# MDB1986.net
KiCad netlist of a schematic drawn in EAGLE
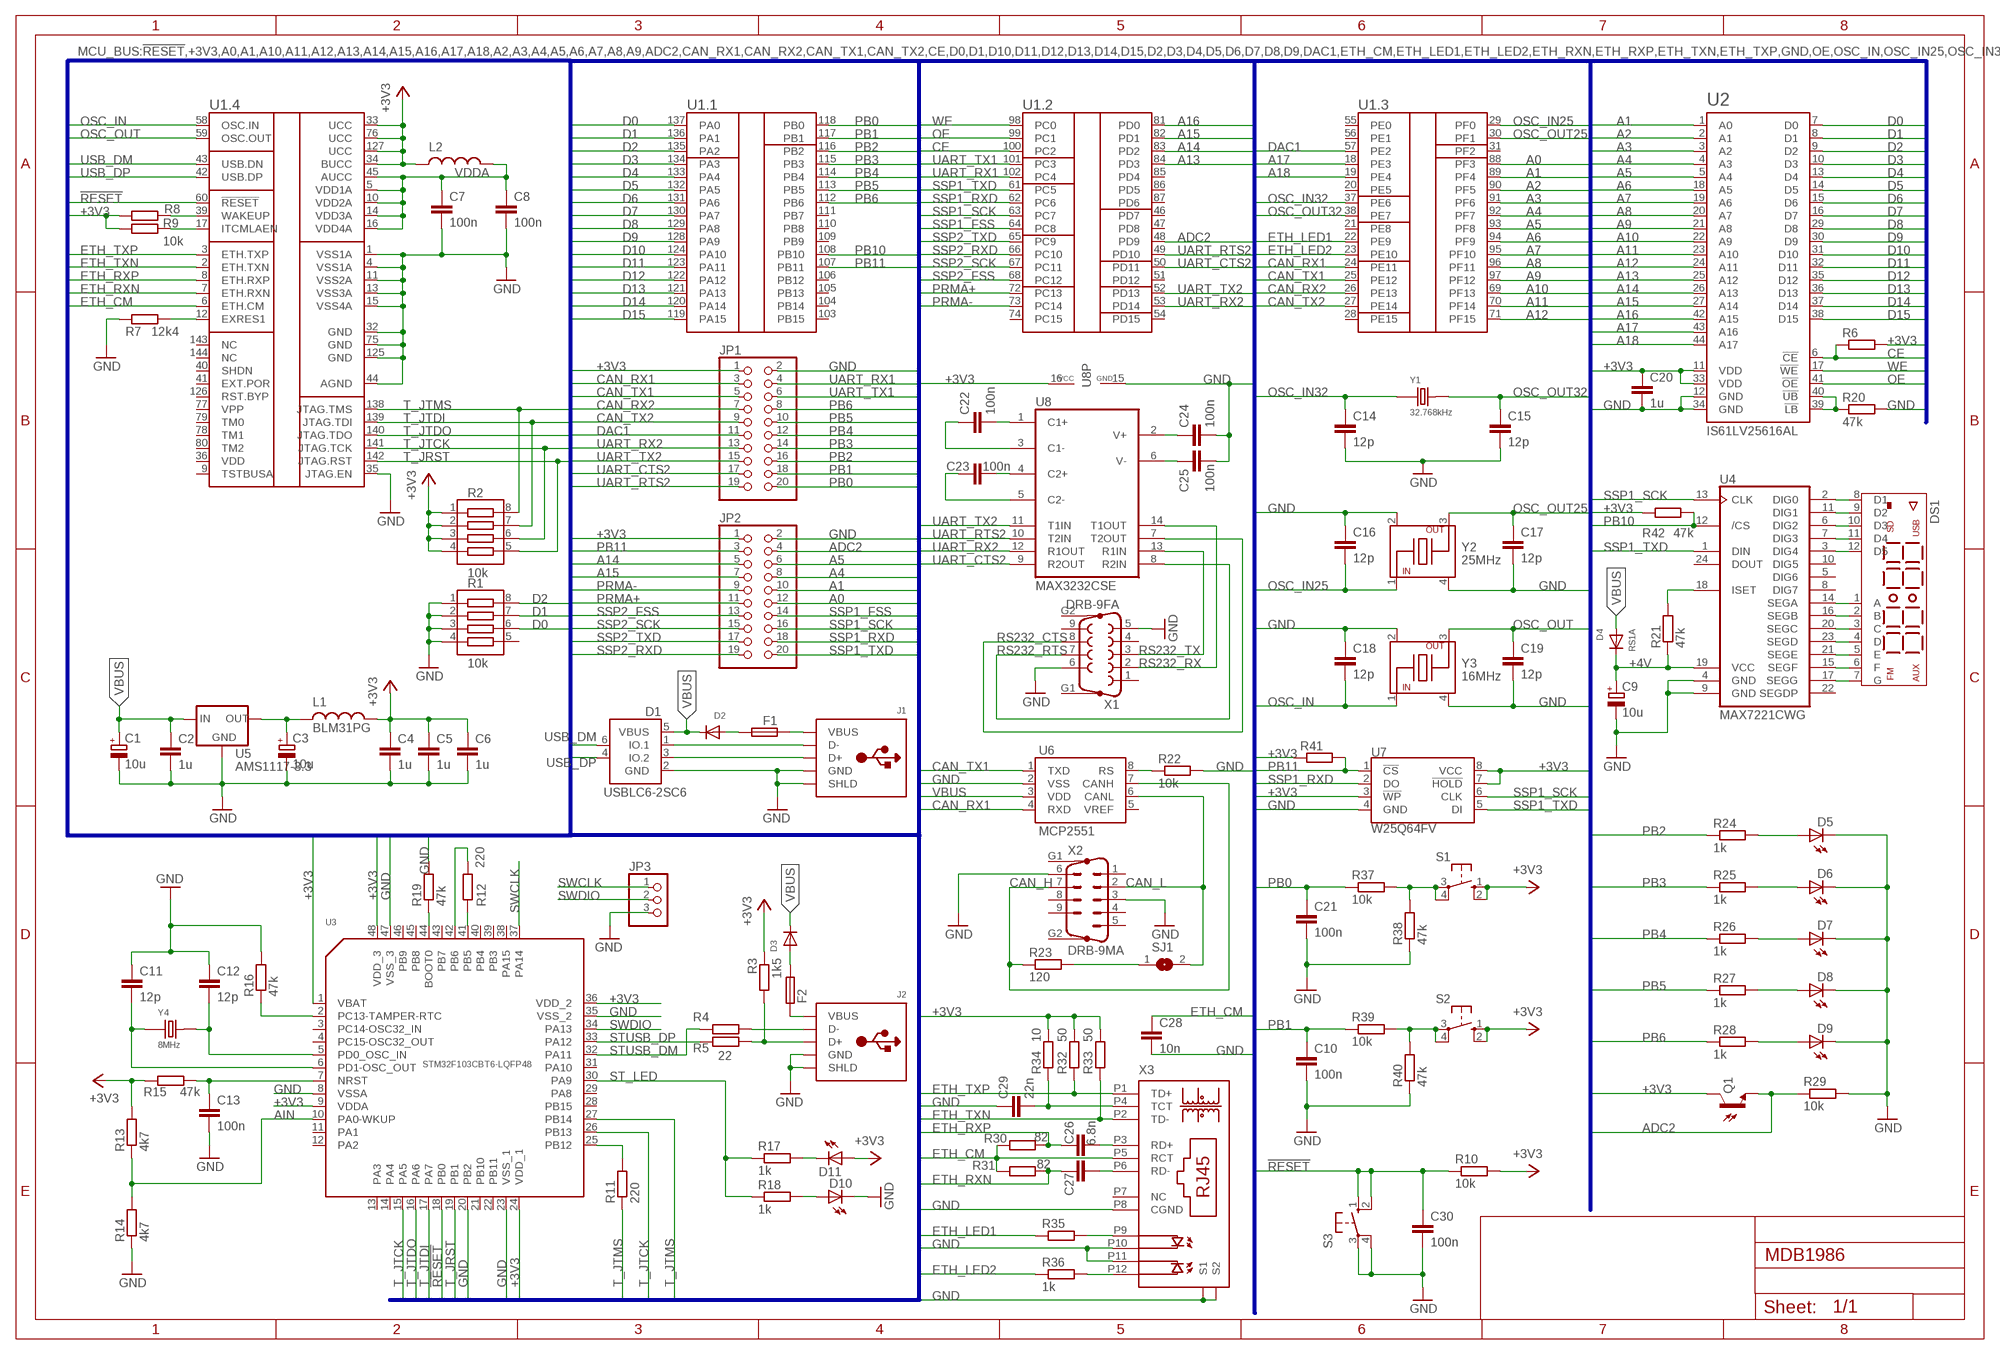
[diagram p0: schematic, sheet 1]

(export (version "E")
  (design (tool "Eeschema 10.0.6"))
  (components
    (comp (ref "C1")
      (value "10u")
      (footprint "eagle-import:RCL-1206F-POL")
      (libsource (lib "eagle-import") (part "CPOL-EU"))
    )
    (comp (ref "C2")
      (value "1u")
      (footprint "eagle-import:RCL-0805F")
      (libsource (lib "eagle-import") (part "C-EU0805"))
    )
    (comp (ref "C3")
      (value "10u")
      (footprint "eagle-import:RCL-1206F-POL")
      (libsource (lib "eagle-import") (part "CPOL-EU"))
    )
    (comp (ref "C4")
      (value "1u")
      (footprint "eagle-import:RCL-0805F")
      (libsource (lib "eagle-import") (part "C-EU0805"))
    )
    (comp (ref "C5")
      (value "1u")
      (footprint "eagle-import:RCL-0805F")
      (libsource (lib "eagle-import") (part "C-EU0805"))
    )
    (comp (ref "C6")
      (value "1u")
      (footprint "eagle-import:RCL-0805F")
      (libsource (lib "eagle-import") (part "C-EU0805"))
    )
    (comp (ref "C7")
      (value "100n")
      (footprint "eagle-import:RCL-0805F")
      (libsource (lib "eagle-import") (part "C-EU0805"))
    )
    (comp (ref "C8")
      (value "100n")
      (footprint "eagle-import:RCL-0805F")
      (libsource (lib "eagle-import") (part "C-EU0805"))
    )
    (comp (ref "C9")
      (value "10u")
      (footprint "eagle-import:RCL-1206F-POL")
      (libsource (lib "eagle-import") (part "CPOL-EU"))
    )
    (comp (ref "C10")
      (value "100n")
      (footprint "eagle-import:RCL-0805F")
      (libsource (lib "eagle-import") (part "C-EU0805"))
    )
    (comp (ref "C11")
      (value "12p")
      (footprint "eagle-import:RCL-0805F")
      (libsource (lib "eagle-import") (part "C-EU0805"))
    )
    (comp (ref "C12")
      (value "12p")
      (footprint "eagle-import:RCL-0805F")
      (libsource (lib "eagle-import") (part "C-EU0805"))
    )
    (comp (ref "C13")
      (value "100n")
      (footprint "eagle-import:RCL-0805F")
      (libsource (lib "eagle-import") (part "C-EU0805"))
    )
    (comp (ref "C14")
      (value "12p")
      (footprint "eagle-import:RCL-0805F")
      (libsource (lib "eagle-import") (part "C-EU0805"))
    )
    (comp (ref "C15")
      (value "12p")
      (footprint "eagle-import:RCL-0805F")
      (libsource (lib "eagle-import") (part "C-EU0805"))
    )
    (comp (ref "C16")
      (value "12p")
      (footprint "eagle-import:RCL-0805F")
      (libsource (lib "eagle-import") (part "C-EU0805"))
    )
    (comp (ref "C17")
      (value "12p")
      (footprint "eagle-import:RCL-0805F")
      (libsource (lib "eagle-import") (part "C-EU0805"))
    )
    (comp (ref "C18")
      (value "12p")
      (footprint "eagle-import:RCL-0805F")
      (libsource (lib "eagle-import") (part "C-EU0805"))
    )
    (comp (ref "C19")
      (value "12p")
      (footprint "eagle-import:RCL-0805F")
      (libsource (lib "eagle-import") (part "C-EU0805"))
    )
    (comp (ref "C20")
      (value "1u")
      (footprint "eagle-import:RCL-0805F")
      (libsource (lib "eagle-import") (part "C-EU0805"))
    )
    (comp (ref "C21")
      (value "100n")
      (footprint "eagle-import:RCL-0805F")
      (libsource (lib "eagle-import") (part "C-EU0805"))
    )
    (comp (ref "C22")
      (value "100n")
      (footprint "eagle-import:RCL-0805F")
      (libsource (lib "eagle-import") (part "C-EU0805"))
    )
    (comp (ref "C23")
      (value "100n")
      (footprint "eagle-import:RCL-0805F")
      (libsource (lib "eagle-import") (part "C-EU0805"))
    )
    (comp (ref "C24")
      (value "100n")
      (footprint "eagle-import:RCL-0805F")
      (libsource (lib "eagle-import") (part "C-EU0805"))
    )
    (comp (ref "C25")
      (value "100n")
      (footprint "eagle-import:RCL-0805F")
      (libsource (lib "eagle-import") (part "C-EU0805"))
    )
    (comp (ref "C26")
      (value "6.8n")
      (footprint "eagle-import:RCL-0805F")
      (libsource (lib "eagle-import") (part "C-EU0805"))
    )
    (comp (ref "C27")
      (value "C-EU0805")
      (footprint "eagle-import:RCL-0805F")
      (libsource (lib "eagle-import") (part "C-EU0805"))
    )
    (comp (ref "C28")
      (value "10n")
      (footprint "eagle-import:RCL-0805F")
      (libsource (lib "eagle-import") (part "C-EU0805"))
    )
    (comp (ref "C29")
      (value "22n")
      (footprint "eagle-import:RCL-0805F")
      (libsource (lib "eagle-import") (part "C-EU0805"))
    )
    (comp (ref "C30")
      (value "100n")
      (footprint "eagle-import:RCL-0805F")
      (libsource (lib "eagle-import") (part "C-EU0805"))
    )
    (comp (ref "D1")
      (value "USBLC6-2SC6")
      (footprint "eagle-import:SOT-23-6L")
      (libsource (lib "eagle-import") (part "USBLC6-2SC6"))
    )
    (comp (ref "D2")
      (value "DIODEDO-214(SMB)")
      (footprint "eagle-import:DO-214AA(SMB)")
      (libsource (lib "eagle-import") (part "DIODEDO-214(SMB)"))
    )
    (comp (ref "D3")
      (value "DIODEDO-214(SMB)")
      (footprint "eagle-import:DO-214AA(SMB)")
      (libsource (lib "eagle-import") (part "DIODEDO-214(SMB)"))
    )
    (comp (ref "D4")
      (value "RS1A")
      (footprint "eagle-import:DO-214AC(SMA)")
      (libsource (lib "eagle-import") (part "DIODEDO-214(SMA)"))
    )
    (comp (ref "D5")
      (value "LED1206")
      (footprint "eagle-import:LED-1206F")
      (libsource (lib "eagle-import") (part "LED1206"))
    )
    (comp (ref "D6")
      (value "LED1206")
      (footprint "eagle-import:LED-1206F")
      (libsource (lib "eagle-import") (part "LED1206"))
    )
    (comp (ref "D7")
      (value "LED1206")
      (footprint "eagle-import:LED-1206F")
      (libsource (lib "eagle-import") (part "LED1206"))
    )
    (comp (ref "D8")
      (value "LED1206")
      (footprint "eagle-import:LED-1206F")
      (libsource (lib "eagle-import") (part "LED1206"))
    )
    (comp (ref "D9")
      (value "LED1206")
      (footprint "eagle-import:LED-1206F")
      (libsource (lib "eagle-import") (part "LED1206"))
    )
    (comp (ref "D10")
      (value "LED1206")
      (footprint "eagle-import:LED-1206F")
      (libsource (lib "eagle-import") (part "LED1206"))
    )
    (comp (ref "D11")
      (value "LED1206")
      (footprint "eagle-import:LED-1206F")
      (libsource (lib "eagle-import") (part "LED1206"))
    )
    (comp (ref "DS1")
      (value "LED-7SEG-12PIN-CC")
      (footprint "eagle-import:LED-7SEG-12P2.54")
      (libsource (lib "eagle-import") (part "LED-7SEG-12PIN-CC"))
    )
    (comp (ref "F1")
      (value "FUSE-NSMF")
      (footprint "eagle-import:RCL-1206F")
      (libsource (lib "eagle-import") (part "FUSE-NSMF"))
    )
    (comp (ref "F2")
      (value "FUSE-NSMF")
      (footprint "eagle-import:RCL-1206F")
      (libsource (lib "eagle-import") (part "FUSE-NSMF"))
    )
    (comp (ref "J1")
      (value "USB-TYPE-B")
      (footprint "eagle-import:USB-TYPE-B-4P")
      (libsource (lib "eagle-import") (part "USB-TYPE-B"))
    )
    (comp (ref "J2")
      (value "USB-TYPE-B")
      (footprint "eagle-import:USB-TYPE-B-4P")
      (libsource (lib "eagle-import") (part "USB-TYPE-B"))
    )
    (comp (ref "JP1")
      (value "PINHD-2X10")
      (footprint "eagle-import:2X10")
      (libsource (lib "eagle-import") (part "PINHD-2X10"))
    )
    (comp (ref "JP2")
      (value "PINHD-2X10")
      (footprint "eagle-import:2X10")
      (libsource (lib "eagle-import") (part "PINHD-2X10"))
    )
    (comp (ref "JP3")
      (value "PINHD-1X3")
      (footprint "eagle-import:1X03")
      (libsource (lib "eagle-import") (part "PINHD-1X3"))
    )
    (comp (ref "L1")
      (value "BLM31PG")
      (footprint "eagle-import:RCL-1206F")
      (libsource (lib "eagle-import") (part "L-EU1206"))
    )
    (comp (ref "L2")
      (value "L-EU1206")
      (footprint "eagle-import:RCL-1206F")
      (libsource (lib "eagle-import") (part "L-EU1206"))
    )
    (comp (ref "Q1")
      (value "PHOTOTRANSISTORPT17-21C-L41-TR8")
      (footprint "eagle-import:PT17-21C-L41-TR8")
      (libsource (lib "eagle-import") (part "PHOTOTRANSISTORPT17-21C-L41-TR8"))
    )
    (comp (ref "R1")
      (value "10k")
      (footprint "eagle-import:RA-1206-X4")
      (libsource (lib "eagle-import") (part "RA-CAT16-F4"))
    )
    (comp (ref "R2")
      (value "10k")
      (footprint "eagle-import:RA-1206-X4")
      (libsource (lib "eagle-import") (part "RA-CAT16-F4"))
    )
    (comp (ref "R3")
      (value "1k5")
      (footprint "eagle-import:RCL-0805F")
      (libsource (lib "eagle-import") (part "R-EU0805"))
    )
    (comp (ref "R4")
      (value "R-EU0805")
      (footprint "eagle-import:RCL-0805F")
      (libsource (lib "eagle-import") (part "R-EU0805"))
    )
    (comp (ref "R5")
      (value "22")
      (footprint "eagle-import:RCL-0805F")
      (libsource (lib "eagle-import") (part "R-EU0805"))
    )
    (comp (ref "R6")
      (value "R-EU0805")
      (footprint "eagle-import:RCL-0805F")
      (libsource (lib "eagle-import") (part "R-EU0805"))
    )
    (comp (ref "R7")
      (value "12k4")
      (footprint "eagle-import:RCL-0805F")
      (libsource (lib "eagle-import") (part "R-EU0805"))
    )
    (comp (ref "R8")
      (value "R-EU0805")
      (footprint "eagle-import:RCL-0805F")
      (libsource (lib "eagle-import") (part "R-EU0805"))
    )
    (comp (ref "R9")
      (value "10k")
      (footprint "eagle-import:RCL-0805F")
      (libsource (lib "eagle-import") (part "R-EU0805"))
    )
    (comp (ref "R10")
      (value "10k")
      (footprint "eagle-import:RCL-0805F")
      (libsource (lib "eagle-import") (part "R-EU0805"))
    )
    (comp (ref "R11")
      (value "220")
      (footprint "eagle-import:RCL-0805F")
      (libsource (lib "eagle-import") (part "R-EU0805"))
    )
    (comp (ref "R12")
      (value "220")
      (footprint "eagle-import:RCL-0805F")
      (libsource (lib "eagle-import") (part "R-EU0805"))
    )
    (comp (ref "R13")
      (value "4k7")
      (footprint "eagle-import:RCL-0805F")
      (libsource (lib "eagle-import") (part "R-EU0805"))
    )
    (comp (ref "R14")
      (value "4k7")
      (footprint "eagle-import:RCL-0805F")
      (libsource (lib "eagle-import") (part "R-EU0805"))
    )
    (comp (ref "R15")
      (value "47k")
      (footprint "eagle-import:RCL-0805F")
      (libsource (lib "eagle-import") (part "R-EU0805"))
    )
    (comp (ref "R16")
      (value "47k")
      (footprint "eagle-import:RCL-0805F")
      (libsource (lib "eagle-import") (part "R-EU0805"))
    )
    (comp (ref "R17")
      (value "1k")
      (footprint "eagle-import:RCL-0805F")
      (libsource (lib "eagle-import") (part "R-EU0805"))
    )
    (comp (ref "R18")
      (value "1k")
      (footprint "eagle-import:RCL-0805F")
      (libsource (lib "eagle-import") (part "R-EU0805"))
    )
    (comp (ref "R19")
      (value "47k")
      (footprint "eagle-import:RCL-0805F")
      (libsource (lib "eagle-import") (part "R-EU0805"))
    )
    (comp (ref "R20")
      (value "47k")
      (footprint "eagle-import:RCL-0805F")
      (libsource (lib "eagle-import") (part "R-EU0805"))
    )
    (comp (ref "R21")
      (value "47k")
      (footprint "eagle-import:RCL-0805F")
      (libsource (lib "eagle-import") (part "R-EU0805"))
    )
    (comp (ref "R22")
      (value "10k")
      (footprint "eagle-import:RCL-0805F")
      (libsource (lib "eagle-import") (part "R-EU0805"))
    )
    (comp (ref "R23")
      (value "120")
      (footprint "eagle-import:RCL-0805F")
      (libsource (lib "eagle-import") (part "R-EU0805"))
    )
    (comp (ref "R24")
      (value "1k")
      (footprint "eagle-import:RCL-0805F")
      (libsource (lib "eagle-import") (part "R-EU0805"))
    )
    (comp (ref "R25")
      (value "1k")
      (footprint "eagle-import:RCL-0805F")
      (libsource (lib "eagle-import") (part "R-EU0805"))
    )
    (comp (ref "R26")
      (value "1k")
      (footprint "eagle-import:RCL-0805F")
      (libsource (lib "eagle-import") (part "R-EU0805"))
    )
    (comp (ref "R27")
      (value "1k")
      (footprint "eagle-import:RCL-0805F")
      (libsource (lib "eagle-import") (part "R-EU0805"))
    )
    (comp (ref "R28")
      (value "1k")
      (footprint "eagle-import:RCL-0805F")
      (libsource (lib "eagle-import") (part "R-EU0805"))
    )
    (comp (ref "R29")
      (value "10k")
      (footprint "eagle-import:RCL-0805F")
      (libsource (lib "eagle-import") (part "R-EU0805"))
    )
    (comp (ref "R30")
      (value "82")
      (footprint "eagle-import:RCL-0805F")
      (libsource (lib "eagle-import") (part "R-EU0805"))
    )
    (comp (ref "R31")
      (value "82")
      (footprint "eagle-import:RCL-0805F")
      (libsource (lib "eagle-import") (part "R-EU0805"))
    )
    (comp (ref "R32")
      (value "50")
      (footprint "eagle-import:RCL-0805F")
      (libsource (lib "eagle-import") (part "R-EU0805"))
    )
    (comp (ref "R33")
      (value "50")
      (footprint "eagle-import:RCL-0805F")
      (libsource (lib "eagle-import") (part "R-EU0805"))
    )
    (comp (ref "R34")
      (value "10")
      (footprint "eagle-import:RCL-0805F")
      (libsource (lib "eagle-import") (part "R-EU0805"))
    )
    (comp (ref "R35")
      (value "R-EU0805")
      (footprint "eagle-import:RCL-0805F")
      (libsource (lib "eagle-import") (part "R-EU0805"))
    )
    (comp (ref "R36")
      (value "1k")
      (footprint "eagle-import:RCL-0805F")
      (libsource (lib "eagle-import") (part "R-EU0805"))
    )
    (comp (ref "R37")
      (value "10k")
      (footprint "eagle-import:RCL-0805F")
      (libsource (lib "eagle-import") (part "R-EU0805"))
    )
    (comp (ref "R38")
      (value "47k")
      (footprint "eagle-import:RCL-0805F")
      (libsource (lib "eagle-import") (part "R-EU0805"))
    )
    (comp (ref "R39")
      (value "10k")
      (footprint "eagle-import:RCL-0805F")
      (libsource (lib "eagle-import") (part "R-EU0805"))
    )
    (comp (ref "R40")
      (value "47k")
      (footprint "eagle-import:RCL-0805F")
      (libsource (lib "eagle-import") (part "R-EU0805"))
    )
    (comp (ref "R41")
      (value "R-EU0805")
      (footprint "eagle-import:RCL-0805F")
      (libsource (lib "eagle-import") (part "R-EU0805"))
    )
    (comp (ref "R42")
      (value "47k")
      (footprint "eagle-import:RCL-0805F")
      (libsource (lib "eagle-import") (part "R-EU0805"))
    )
    (comp (ref "S1")
      (value "SWITCH-10-XX")
      (footprint "eagle-import:BUTTON-B3F-10XX")
      (fields (field (name "MPN") "B3F-1000"))
      (libsource (lib "eagle-import") (part "SWITCH-10-XX"))
    )
    (comp (ref "S2")
      (value "SWITCH-10-XX")
      (footprint "eagle-import:BUTTON-B3F-10XX")
      (fields (field (name "MPN") "B3F-1000"))
      (libsource (lib "eagle-import") (part "SWITCH-10-XX"))
    )
    (comp (ref "S3")
      (value "SWITCH-10-XX")
      (footprint "eagle-import:BUTTON-B3F-10XX")
      (fields (field (name "MPN") "B3F-1000"))
      (libsource (lib "eagle-import") (part "SWITCH-10-XX"))
    )
    (comp (ref "SJ1") (value "SJ") (footprint "eagle-import:SJ") (libsource (lib "eagle-import") (part "SJ")))
    (comp (ref "U1")
      (value "MCU-K1986BE1QI")
      (footprint "eagle-import:LQFP144-0.5-20X20M")
      (libsource (lib "eagle-import") (part "MCU-K1986BE1QI"))
    )
    (comp (ref "U2")
      (value "IS61LV25616AL")
      (footprint "eagle-import:TSOP2-44-400BF")
      (libsource (lib "eagle-import") (part "IS61LV25616AL"))
    )
    (comp (ref "U3")
      (value "STM32F103CBT6-LQFP48")
      (footprint "eagle-import:LQFP48-0.5-7X7MM")
      (fields (field (name "MPN") "STM32F103CBT6"))
      (libsource (lib "eagle-import") (part "MCU-STM32F103CBT6"))
    )
    (comp (ref "U4")
      (value "MAX7221CWG")
      (footprint "eagle-import:SO24W")
      (libsource (lib "eagle-import") (part "MAX7221CWG"))
    )
    (comp (ref "U5")
      (value "AMS1117-3.3")
      (footprint "eagle-import:SOT223")
      (libsource (lib "eagle-import") (part "AMS1117-3.3"))
    )
    (comp (ref "U6")
      (value "MCP2551")
      (footprint "eagle-import:SO08")
      (libsource (lib "eagle-import") (part "MCP2551"))
    )
    (comp (ref "U7")
      (value "W25Q64FV")
      (footprint "eagle-import:SOIC-8")
      (libsource (lib "eagle-import") (part "W25Q64FVSS"))
    )
    (comp (ref "U8")
      (value "MAX3232CSE")
      (footprint "eagle-import:SO16")
      (libsource (lib "eagle-import") (part "MAX3232SEC"))
    )
    (comp (ref "X1")
      (value "DRB-9FA")
      (footprint "eagle-import:F09HP")
      (libsource (lib "eagle-import") (part "F09HP"))
    )
    (comp (ref "X2")
      (value "DRB-9MA")
      (footprint "eagle-import:M09HP")
      (libsource (lib "eagle-import") (part "M09HP"))
    )
    (comp (ref "X3")
      (value "HR911105A")
      (footprint "eagle-import:RJ45")
      (libsource (lib "eagle-import") (part "HR911105A"))
    )
    (comp (ref "Y1")
      (value "32.768kHz")
      (footprint "eagle-import:XTAL-FC-135")
      (libsource (lib "eagle-import") (part "CRYSTAL-FC-135"))
    )
    (comp (ref "Y2")
      (value "25MHz")
      (footprint "eagle-import:XTAL-FA-238")
      (libsource (lib "eagle-import") (part "CRYSTAL-FA-238"))
    )
    (comp (ref "Y3")
      (value "16MHz")
      (footprint "eagle-import:XTAL-FA-238")
      (libsource (lib "eagle-import") (part "CRYSTAL-FA-238"))
    )
    (comp (ref "Y4")
      (value "8MHz")
      (footprint "eagle-import:XTAL-NX3225")
      (libsource (lib "eagle-import") (part "CRYSTAL-NX3225"))
    )
  )
  (nets
    (net (code "9") (name "+3V3") (class "Default")
      (node (ref "C20") (pin "1") (pinfunction "1_1") (pintype "passive"))
      (node (ref "C4") (pin "1") (pinfunction "1_1") (pintype "passive"))
      (node (ref "C5") (pin "1") (pinfunction "1_1") (pintype "passive"))
      (node (ref "C6") (pin "1") (pinfunction "1_1") (pintype "passive"))
      (node (ref "D11") (pin "A") (pinfunction "A_A") (pintype "passive"))
      (node (ref "JP1") (pin "1") (pinfunction "1_1") (pintype "passive"))
      (node (ref "JP2") (pin "1") (pinfunction "1_1") (pintype "passive"))
      (node (ref "L1") (pin "2") (pinfunction "2_2") (pintype "passive"))
      (node (ref "L2") (pin "1") (pinfunction "1_1") (pintype "passive"))
      (node (ref "Q1") (pin "C") (pinfunction "C_C") (pintype "passive"))
      (node (ref "R10") (pin "2") (pinfunction "2_2") (pintype "passive"))
      (node (ref "R13") (pin "2") (pinfunction "2_2") (pintype "passive"))
      (node (ref "R15") (pin "1") (pinfunction "1_1") (pintype "passive"))
      (node (ref "R2") (pin "1") (pinfunction "P.1_1") (pintype "passive"))
      (node (ref "R2") (pin "2") (pinfunction "P.2_2") (pintype "passive"))
      (node (ref "R2") (pin "3") (pinfunction "P.3_3") (pintype "passive"))
      (node (ref "R2") (pin "4") (pinfunction "P.4_4") (pintype "passive"))
      (node (ref "R3") (pin "1") (pinfunction "1_1") (pintype "passive"))
      (node (ref "R32") (pin "2") (pinfunction "2_2") (pintype "passive"))
      (node (ref "R33") (pin "2") (pinfunction "2_2") (pintype "passive"))
      (node (ref "R34") (pin "2") (pinfunction "2_2") (pintype "passive"))
      (node (ref "R41") (pin "1") (pinfunction "1_1") (pintype "passive"))
      (node (ref "R42") (pin "1") (pinfunction "1_1") (pintype "passive"))
      (node (ref "R6") (pin "2") (pinfunction "2_2") (pintype "passive"))
      (node (ref "R8") (pin "1") (pinfunction "1_1") (pintype "passive"))
      (node (ref "R9") (pin "1") (pinfunction "1_1") (pintype "passive"))
      (node (ref "S1") (pin "1") (pinfunction "S_1") (pintype "passive"))
      (node (ref "S1") (pin "2") (pinfunction "S1_2") (pintype "passive"))
      (node (ref "S2") (pin "1") (pinfunction "S_1") (pintype "passive"))
      (node (ref "S2") (pin "2") (pinfunction "S1_2") (pintype "passive"))
      (node (ref "U1") (pin "127") (pinfunction "UCC_127") (pintype "bidirectional"))
      (node (ref "U1") (pin "33") (pinfunction "UCC_33") (pintype "bidirectional"))
      (node (ref "U1") (pin "34") (pinfunction "BUCC_34") (pintype "bidirectional"))
      (node (ref "U1") (pin "76") (pinfunction "UCC_76") (pintype "bidirectional"))
      (node (ref "U2") (pin "11") (pinfunction "VDD_11") (pintype "power_in"))
      (node (ref "U2") (pin "33") (pinfunction "VDD_33") (pintype "power_in"))
      (node (ref "U3") (pin "1") (pinfunction "VBAT_1") (pintype "bidirectional"))
      (node (ref "U3") (pin "24") (pinfunction "VDD_1_24") (pintype "bidirectional"))
      (node (ref "U3") (pin "36") (pinfunction "VDD_2_36") (pintype "bidirectional"))
      (node (ref "U3") (pin "48") (pinfunction "VDD_3_48") (pintype "bidirectional"))
      (node (ref "U3") (pin "9") (pinfunction "VDDA_9") (pintype "bidirectional"))
      (node (ref "U7") (pin "3") (pinfunction "~{WP}_3") (pintype "bidirectional"))
      (node (ref "U7") (pin "7") (pinfunction "~{HOLD}_7") (pintype "bidirectional"))
      (node (ref "U7") (pin "8") (pinfunction "VCC_8") (pintype "bidirectional"))
      (node (ref "U8") (pin "16") (pinfunction "VCC_16") (pintype "power_in"))
    )
    (net (code "10") (name "/+4V") (class "Default")
      (node (ref "C9") (pin "+") (pinfunction "+_+") (pintype "passive"))
      (node (ref "D4") (pin "C") (pinfunction "C_C") (pintype "passive"))
      (node (ref "R21") (pin "1") (pinfunction "1_1") (pintype "passive"))
      (node (ref "U4") (pin "19") (pinfunction "VCC_19") (pintype "power_in"))
    )
    (net (code "11") (name "/A0") (class "Default")
      (node (ref "JP2") (pin "12") (pinfunction "12_12") (pintype "passive"))
      (node (ref "U1") (pin "88") (pinfunction "PF3_88") (pintype "bidirectional"))
    )
    (net (code "12") (name "/A1") (class "Default")
      (node (ref "JP2") (pin "10") (pinfunction "10_10") (pintype "passive"))
      (node (ref "U1") (pin "89") (pinfunction "PF4_89") (pintype "bidirectional"))
      (node (ref "U2") (pin "1") (pinfunction "A0_1") (pintype "input"))
    )
    (net (code "13") (name "/A2") (class "Default")
      (node (ref "U1") (pin "90") (pinfunction "PF5_90") (pintype "bidirectional"))
      (node (ref "U2") (pin "2") (pinfunction "A1_2") (pintype "input"))
    )
    (net (code "14") (name "/A3") (class "Default")
      (node (ref "U1") (pin "91") (pinfunction "PF6_91") (pintype "bidirectional"))
      (node (ref "U2") (pin "3") (pinfunction "A2_3") (pintype "input"))
    )
    (net (code "15") (name "/A4") (class "Default")
      (node (ref "JP2") (pin "8") (pinfunction "8_8") (pintype "passive"))
      (node (ref "U1") (pin "92") (pinfunction "PF7_92") (pintype "bidirectional"))
      (node (ref "U2") (pin "4") (pinfunction "A3_4") (pintype "input"))
    )
    (net (code "16") (name "/A5") (class "Default")
      (node (ref "JP2") (pin "6") (pinfunction "6_6") (pintype "passive"))
      (node (ref "U1") (pin "93") (pinfunction "PF8_93") (pintype "bidirectional"))
      (node (ref "U2") (pin "5") (pinfunction "A4_5") (pintype "input"))
    )
    (net (code "17") (name "/A6") (class "Default")
      (node (ref "U1") (pin "94") (pinfunction "PF9_94") (pintype "bidirectional"))
      (node (ref "U2") (pin "18") (pinfunction "A5_18") (pintype "input"))
    )
    (net (code "18") (name "/A7") (class "Default")
      (node (ref "U1") (pin "95") (pinfunction "PF10_95") (pintype "bidirectional"))
      (node (ref "U2") (pin "19") (pinfunction "A6_19") (pintype "input"))
    )
    (net (code "19") (name "/A8") (class "Default")
      (node (ref "U1") (pin "96") (pinfunction "PF11_96") (pintype "bidirectional"))
      (node (ref "U2") (pin "20") (pinfunction "A7_20") (pintype "input"))
    )
    (net (code "20") (name "/A9") (class "Default")
      (node (ref "U1") (pin "97") (pinfunction "PF12_97") (pintype "bidirectional"))
      (node (ref "U2") (pin "21") (pinfunction "A8_21") (pintype "input"))
    )
    (net (code "21") (name "/A10") (class "Default")
      (node (ref "U1") (pin "69") (pinfunction "PF13_69") (pintype "bidirectional"))
      (node (ref "U2") (pin "22") (pinfunction "A9_22") (pintype "input"))
    )
    (net (code "22") (name "/A11") (class "Default")
      (node (ref "U1") (pin "70") (pinfunction "PF14_70") (pintype "bidirectional"))
      (node (ref "U2") (pin "23") (pinfunction "A10_23") (pintype "input"))
    )
    (net (code "23") (name "/A12") (class "Default")
      (node (ref "U1") (pin "71") (pinfunction "PF15_71") (pintype "bidirectional"))
      (node (ref "U2") (pin "24") (pinfunction "A11_24") (pintype "input"))
    )
    (net (code "24") (name "/A13") (class "Default")
      (node (ref "U1") (pin "84") (pinfunction "PD3_84") (pintype "bidirectional"))
      (node (ref "U2") (pin "25") (pinfunction "A12_25") (pintype "input"))
    )
    (net (code "25") (name "/A14") (class "Default")
      (node (ref "JP2") (pin "5") (pinfunction "5_5") (pintype "passive"))
      (node (ref "U1") (pin "83") (pinfunction "PD2_83") (pintype "bidirectional"))
      (node (ref "U2") (pin "26") (pinfunction "A13_26") (pintype "input"))
    )
    (net (code "26") (name "/A15") (class "Default")
      (node (ref "JP2") (pin "7") (pinfunction "7_7") (pintype "passive"))
      (node (ref "U1") (pin "82") (pinfunction "PD1_82") (pintype "bidirectional"))
      (node (ref "U2") (pin "27") (pinfunction "A14_27") (pintype "input"))
    )
    (net (code "27") (name "/A16") (class "Default")
      (node (ref "U1") (pin "81") (pinfunction "PD0_81") (pintype "bidirectional"))
      (node (ref "U2") (pin "42") (pinfunction "A15_42") (pintype "input"))
    )
    (net (code "28") (name "/A17") (class "Default")
      (node (ref "U1") (pin "18") (pinfunction "PE3_18") (pintype "bidirectional"))
      (node (ref "U2") (pin "43") (pinfunction "A16_43") (pintype "input"))
    )
    (net (code "29") (name "/A18") (class "Default")
      (node (ref "U1") (pin "19") (pinfunction "PE4_19") (pintype "bidirectional"))
      (node (ref "U2") (pin "44") (pinfunction "A17_44") (pintype "input"))
    )
    (net (code "30") (name "/ADC2") (class "Default")
      (node (ref "JP2") (pin "4") (pinfunction "4_4") (pintype "passive"))
      (node (ref "Q1") (pin "E") (pinfunction "E_E") (pintype "passive"))
      (node (ref "R29") (pin "1") (pinfunction "1_1") (pintype "passive"))
      (node (ref "U1") (pin "48") (pinfunction "PD9_48") (pintype "bidirectional"))
    )
    (net (code "31") (name "/AIN") (class "Default")
      (node (ref "R13") (pin "1") (pinfunction "1_1") (pintype "passive"))
      (node (ref "R14") (pin "2") (pinfunction "2_2") (pintype "passive"))
      (node (ref "U3") (pin "10") (pinfunction "PA0-WKUP_10") (pintype "bidirectional"))
    )
    (net (code "32") (name "/CAN_H") (class "Default")
      (node (ref "R23") (pin "1") (pinfunction "1_1") (pintype "passive"))
      (node (ref "U6") (pin "7") (pinfunction "CANH_7") (pintype "bidirectional"))
      (node (ref "X2") (pin "7") (pinfunction "7_7") (pintype "passive"))
    )
    (net (code "33") (name "/CAN_L") (class "Default")
      (node (ref "SJ1") (pin "2") (pinfunction "2_2") (pintype "passive"))
      (node (ref "U6") (pin "6") (pinfunction "CANL_6") (pintype "bidirectional"))
      (node (ref "X2") (pin "2") (pinfunction "2_2") (pintype "passive"))
    )
    (net (code "34") (name "/CAN_RX1") (class "Default")
      (node (ref "JP1") (pin "3") (pinfunction "3_3") (pintype "passive"))
      (node (ref "U1") (pin "24") (pinfunction "PE11_24") (pintype "bidirectional"))
      (node (ref "U6") (pin "4") (pinfunction "RXD_4") (pintype "bidirectional"))
    )
    (net (code "35") (name "/CAN_RX2") (class "Default")
      (node (ref "JP1") (pin "7") (pinfunction "7_7") (pintype "passive"))
      (node (ref "U1") (pin "26") (pinfunction "PE13_26") (pintype "bidirectional"))
    )
    (net (code "36") (name "/CAN_TX1") (class "Default")
      (node (ref "JP1") (pin "5") (pinfunction "5_5") (pintype "passive"))
      (node (ref "U1") (pin "25") (pinfunction "PE12_25") (pintype "bidirectional"))
      (node (ref "U6") (pin "1") (pinfunction "TXD_1") (pintype "bidirectional"))
    )
    (net (code "37") (name "/CAN_TX2") (class "Default")
      (node (ref "JP1") (pin "9") (pinfunction "9_9") (pintype "passive"))
      (node (ref "U1") (pin "27") (pinfunction "PE14_27") (pintype "bidirectional"))
    )
    (net (code "38") (name "/CE") (class "Default")
      (node (ref "R6") (pin "1") (pinfunction "1_1") (pintype "passive"))
      (node (ref "U1") (pin "100") (pinfunction "PC2_100") (pintype "bidirectional"))
      (node (ref "U2") (pin "6") (pinfunction "~{CE}_6") (pintype "input"))
    )
    (net (code "39") (name "/D0") (class "Default")
      (node (ref "R1") (pin "6") (pinfunction "P.6_6") (pintype "passive"))
      (node (ref "U1") (pin "137") (pinfunction "PA0_137") (pintype "bidirectional"))
      (node (ref "U2") (pin "7") (pinfunction "D0_7") (pintype "bidirectional"))
    )
    (net (code "40") (name "/D1") (class "Default")
      (node (ref "R1") (pin "7") (pinfunction "P.7_7") (pintype "passive"))
      (node (ref "U1") (pin "136") (pinfunction "PA1_136") (pintype "bidirectional"))
      (node (ref "U2") (pin "8") (pinfunction "D1_8") (pintype "bidirectional"))
    )
    (net (code "41") (name "/D2") (class "Default")
      (node (ref "R1") (pin "8") (pinfunction "P.8_8") (pintype "passive"))
      (node (ref "U1") (pin "135") (pinfunction "PA2_135") (pintype "bidirectional"))
      (node (ref "U2") (pin "9") (pinfunction "D2_9") (pintype "bidirectional"))
    )
    (net (code "42") (name "/D3") (class "Default")
      (node (ref "U1") (pin "134") (pinfunction "PA3_134") (pintype "bidirectional"))
      (node (ref "U2") (pin "10") (pinfunction "D3_10") (pintype "bidirectional"))
    )
    (net (code "43") (name "/D4") (class "Default")
      (node (ref "U1") (pin "133") (pinfunction "PA4_133") (pintype "bidirectional"))
      (node (ref "U2") (pin "13") (pinfunction "D4_13") (pintype "bidirectional"))
    )
    (net (code "44") (name "/D5") (class "Default")
      (node (ref "U1") (pin "132") (pinfunction "PA5_132") (pintype "bidirectional"))
      (node (ref "U2") (pin "14") (pinfunction "D5_14") (pintype "bidirectional"))
    )
    (net (code "45") (name "/D6") (class "Default")
      (node (ref "U1") (pin "131") (pinfunction "PA6_131") (pintype "bidirectional"))
      (node (ref "U2") (pin "15") (pinfunction "D6_15") (pintype "bidirectional"))
    )
    (net (code "46") (name "/D7") (class "Default")
      (node (ref "U1") (pin "130") (pinfunction "PA7_130") (pintype "bidirectional"))
      (node (ref "U2") (pin "16") (pinfunction "D7_16") (pintype "bidirectional"))
    )
    (net (code "47") (name "/D8") (class "Default")
      (node (ref "U1") (pin "129") (pinfunction "PA8_129") (pintype "bidirectional"))
      (node (ref "U2") (pin "29") (pinfunction "D8_29") (pintype "bidirectional"))
    )
    (net (code "48") (name "/D9") (class "Default")
      (node (ref "U1") (pin "128") (pinfunction "PA9_128") (pintype "bidirectional"))
      (node (ref "U2") (pin "30") (pinfunction "D9_30") (pintype "bidirectional"))
    )
    (net (code "49") (name "/D10") (class "Default")
      (node (ref "U1") (pin "124") (pinfunction "PA10_124") (pintype "bidirectional"))
      (node (ref "U2") (pin "31") (pinfunction "D10_31") (pintype "bidirectional"))
    )
    (net (code "50") (name "/D11") (class "Default")
      (node (ref "U1") (pin "123") (pinfunction "PA11_123") (pintype "bidirectional"))
      (node (ref "U2") (pin "32") (pinfunction "D11_32") (pintype "bidirectional"))
    )
    (net (code "51") (name "/D12") (class "Default")
      (node (ref "U1") (pin "122") (pinfunction "PA12_122") (pintype "bidirectional"))
      (node (ref "U2") (pin "35") (pinfunction "D12_35") (pintype "bidirectional"))
    )
    (net (code "52") (name "/D13") (class "Default")
      (node (ref "U1") (pin "121") (pinfunction "PA13_121") (pintype "bidirectional"))
      (node (ref "U2") (pin "36") (pinfunction "D13_36") (pintype "bidirectional"))
    )
    (net (code "53") (name "/D14") (class "Default")
      (node (ref "U1") (pin "120") (pinfunction "PA14_120") (pintype "bidirectional"))
      (node (ref "U2") (pin "37") (pinfunction "D14_37") (pintype "bidirectional"))
    )
    (net (code "54") (name "/D15") (class "Default")
      (node (ref "U1") (pin "119") (pinfunction "PA15_119") (pintype "bidirectional"))
      (node (ref "U2") (pin "38") (pinfunction "D15_38") (pintype "bidirectional"))
    )
    (net (code "55") (name "/DAC1") (class "Default")
      (node (ref "JP1") (pin "11") (pinfunction "11_11") (pintype "passive"))
      (node (ref "U1") (pin "57") (pinfunction "PE2_57") (pintype "bidirectional"))
    )
    (net (code "56") (name "/ETH_CM") (class "Default")
      (node (ref "C28") (pin "1") (pinfunction "1_1") (pintype "passive"))
      (node (ref "R30") (pin "1") (pinfunction "1_1") (pintype "passive"))
      (node (ref "R31") (pin "1") (pinfunction "1_1") (pintype "passive"))
      (node (ref "U1") (pin "6") (pinfunction "ETH.CM_6") (pintype "bidirectional"))
      (node (ref "X3") (pin "P5") (pinfunction "RCT_P5") (pintype "passive"))
    )
    (net (code "57") (name "/ETH_LED1") (class "Default")
      (node (ref "R35") (pin "1") (pinfunction "1_1") (pintype "passive"))
      (node (ref "U1") (pin "22") (pinfunction "PE9_22") (pintype "bidirectional"))
    )
    (net (code "58") (name "/ETH_LED2") (class "Default")
      (node (ref "R36") (pin "1") (pinfunction "1_1") (pintype "passive"))
      (node (ref "U1") (pin "23") (pinfunction "PE10_23") (pintype "bidirectional"))
    )
    (net (code "59") (name "/ETH_RXN") (class "Default")
      (node (ref "C27") (pin "1") (pinfunction "1_1") (pintype "passive"))
      (node (ref "R31") (pin "2") (pinfunction "2_2") (pintype "passive"))
      (node (ref "U1") (pin "7") (pinfunction "ETH.RXN_7") (pintype "bidirectional"))
    )
    (net (code "60") (name "/ETH_RXP") (class "Default")
      (node (ref "C26") (pin "1") (pinfunction "1_1") (pintype "passive"))
      (node (ref "R30") (pin "2") (pinfunction "2_2") (pintype "passive"))
      (node (ref "U1") (pin "8") (pinfunction "ETH.RXP_8") (pintype "bidirectional"))
    )
    (net (code "61") (name "/ETH_TXN") (class "Default")
      (node (ref "R33") (pin "1") (pinfunction "1_1") (pintype "passive"))
      (node (ref "U1") (pin "2") (pinfunction "ETH.TXN_2") (pintype "bidirectional"))
      (node (ref "X3") (pin "P2") (pinfunction "TD-_P2") (pintype "passive"))
    )
    (net (code "62") (name "/ETH_TXP") (class "Default")
      (node (ref "R32") (pin "1") (pinfunction "1_1") (pintype "passive"))
      (node (ref "U1") (pin "3") (pinfunction "ETH.TXP_3") (pintype "bidirectional"))
      (node (ref "X3") (pin "P1") (pinfunction "TD+_P1") (pintype "passive"))
    )
    (net (code "63") (name "/OE") (class "Default")
      (node (ref "U1") (pin "99") (pinfunction "PC1_99") (pintype "bidirectional"))
      (node (ref "U2") (pin "41") (pinfunction "~{OE}_41") (pintype "input"))
    )
    (net (code "64") (name "/OSC_IN") (class "Default")
      (node (ref "C18") (pin "2") (pinfunction "2_2") (pintype "passive"))
      (node (ref "U1") (pin "58") (pinfunction "OSC.IN_58") (pintype "bidirectional"))
      (node (ref "Y3") (pin "1") (pinfunction "X.IN_1") (pintype "bidirectional"))
    )
    (net (code "65") (name "/OSC_IN25") (class "Default")
      (node (ref "C16") (pin "2") (pinfunction "2_2") (pintype "passive"))
      (node (ref "U1") (pin "29") (pinfunction "PF0_29") (pintype "bidirectional"))
      (node (ref "Y2") (pin "1") (pinfunction "X.IN_1") (pintype "bidirectional"))
    )
    (net (code "66") (name "/OSC_IN32") (class "Default")
      (node (ref "C14") (pin "1") (pinfunction "1_1") (pintype "passive"))
      (node (ref "U1") (pin "37") (pinfunction "PE6_37") (pintype "bidirectional"))
      (node (ref "Y1") (pin "1") (pinfunction "1_1") (pintype "passive"))
    )
    (net (code "67") (name "/OSC_OUT") (class "Default")
      (node (ref "C19") (pin "1") (pinfunction "1_1") (pintype "passive"))
      (node (ref "U1") (pin "59") (pinfunction "OSC.OUT_59") (pintype "bidirectional"))
      (node (ref "Y3") (pin "3") (pinfunction "X.OUT_3") (pintype "bidirectional"))
    )
    (net (code "68") (name "/OSC_OUT25") (class "Default")
      (node (ref "C17") (pin "1") (pinfunction "1_1") (pintype "passive"))
      (node (ref "U1") (pin "30") (pinfunction "PF1_30") (pintype "bidirectional"))
      (node (ref "Y2") (pin "3") (pinfunction "X.OUT_3") (pintype "bidirectional"))
    )
    (net (code "69") (name "/OSC_OUT32") (class "Default")
      (node (ref "C15") (pin "1") (pinfunction "1_1") (pintype "passive"))
      (node (ref "U1") (pin "38") (pinfunction "PE7_38") (pintype "bidirectional"))
      (node (ref "Y1") (pin "2") (pinfunction "2_2") (pintype "passive"))
    )
    (net (code "70") (name "/PB0") (class "Default")
      (node (ref "C21") (pin "1") (pinfunction "1_1") (pintype "passive"))
      (node (ref "JP1") (pin "20") (pinfunction "20_20") (pintype "passive"))
      (node (ref "R37") (pin "1") (pinfunction "1_1") (pintype "passive"))
      (node (ref "U1") (pin "118") (pinfunction "PB0_118") (pintype "bidirectional"))
    )
    (net (code "71") (name "/PB1") (class "Default")
      (node (ref "C10") (pin "1") (pinfunction "1_1") (pintype "passive"))
      (node (ref "JP1") (pin "18") (pinfunction "18_18") (pintype "passive"))
      (node (ref "R39") (pin "1") (pinfunction "1_1") (pintype "passive"))
      (node (ref "U1") (pin "117") (pinfunction "PB1_117") (pintype "bidirectional"))
    )
    (net (code "72") (name "/PB2") (class "Default")
      (node (ref "JP1") (pin "16") (pinfunction "16_16") (pintype "passive"))
      (node (ref "R24") (pin "1") (pinfunction "1_1") (pintype "passive"))
      (node (ref "U1") (pin "116") (pinfunction "PB2_116") (pintype "bidirectional"))
    )
    (net (code "73") (name "/PB3") (class "Default")
      (node (ref "JP1") (pin "14") (pinfunction "14_14") (pintype "passive"))
      (node (ref "R25") (pin "1") (pinfunction "1_1") (pintype "passive"))
      (node (ref "U1") (pin "115") (pinfunction "PB3_115") (pintype "bidirectional"))
    )
    (net (code "74") (name "/PB4") (class "Default")
      (node (ref "JP1") (pin "12") (pinfunction "12_12") (pintype "passive"))
      (node (ref "R26") (pin "1") (pinfunction "1_1") (pintype "passive"))
      (node (ref "U1") (pin "114") (pinfunction "PB4_114") (pintype "bidirectional"))
    )
    (net (code "75") (name "/PB5") (class "Default")
      (node (ref "JP1") (pin "10") (pinfunction "10_10") (pintype "passive"))
      (node (ref "R27") (pin "1") (pinfunction "1_1") (pintype "passive"))
      (node (ref "U1") (pin "113") (pinfunction "PB5_113") (pintype "bidirectional"))
    )
    (net (code "76") (name "/PB6") (class "Default")
      (node (ref "JP1") (pin "8") (pinfunction "8_8") (pintype "passive"))
      (node (ref "R28") (pin "1") (pinfunction "1_1") (pintype "passive"))
      (node (ref "U1") (pin "112") (pinfunction "PB6_112") (pintype "bidirectional"))
    )
    (net (code "77") (name "/PB10") (class "Default")
      (node (ref "R42") (pin "2") (pinfunction "2_2") (pintype "passive"))
      (node (ref "U1") (pin "108") (pinfunction "PB10_108") (pintype "bidirectional"))
      (node (ref "U4") (pin "12") (pinfunction "/CS_12") (pintype "input"))
    )
    (net (code "78") (name "/PB11") (class "Default")
      (node (ref "JP2") (pin "3") (pinfunction "3_3") (pintype "passive"))
      (node (ref "R41") (pin "2") (pinfunction "2_2") (pintype "passive"))
      (node (ref "U1") (pin "107") (pinfunction "PB11_107") (pintype "bidirectional"))
      (node (ref "U7") (pin "1") (pinfunction "~{CS}_1") (pintype "bidirectional"))
    )
    (net (code "79") (name "/PRMA+") (class "Default")
      (node (ref "JP2") (pin "11") (pinfunction "11_11") (pintype "passive"))
      (node (ref "U1") (pin "72") (pinfunction "PC13_72") (pintype "bidirectional"))
    )
    (net (code "80") (name "/PRMA-") (class "Default")
      (node (ref "JP2") (pin "9") (pinfunction "9_9") (pintype "passive"))
      (node (ref "U1") (pin "73") (pinfunction "PC14_73") (pintype "bidirectional"))
    )
    (net (code "81") (name "/RS232_CTS") (class "Default")
      (node (ref "U8") (pin "7") (pinfunction "T2OUT_7") (pintype "output"))
      (node (ref "X1") (pin "8") (pinfunction "8_8") (pintype "passive"))
    )
    (net (code "82") (name "/RS232_RTS") (class "Default")
      (node (ref "U8") (pin "8") (pinfunction "R2IN_8") (pintype "input"))
      (node (ref "X1") (pin "7") (pinfunction "7_7") (pintype "passive"))
    )
    (net (code "83") (name "/RS232_RX") (class "Default")
      (node (ref "U8") (pin "14") (pinfunction "T1OUT_14") (pintype "output"))
      (node (ref "X1") (pin "2") (pinfunction "2_2") (pintype "passive"))
    )
    (net (code "84") (name "/RS232_TX") (class "Default")
      (node (ref "U8") (pin "13") (pinfunction "R1IN_13") (pintype "input"))
      (node (ref "X1") (pin "3") (pinfunction "3_3") (pintype "passive"))
    )
    (net (code "85") (name "/SSP1_FSS") (class "Default")
      (node (ref "JP2") (pin "14") (pinfunction "14_14") (pintype "passive"))
      (node (ref "U1") (pin "64") (pinfunction "PC8_64") (pintype "bidirectional"))
    )
    (net (code "86") (name "/SSP1_RXD") (class "Default")
      (node (ref "JP2") (pin "18") (pinfunction "18_18") (pintype "passive"))
      (node (ref "U1") (pin "62") (pinfunction "PC6_62") (pintype "bidirectional"))
      (node (ref "U7") (pin "2") (pinfunction "DO_2") (pintype "bidirectional"))
    )
    (net (code "87") (name "/SSP1_SCK") (class "Default")
      (node (ref "JP2") (pin "16") (pinfunction "16_16") (pintype "passive"))
      (node (ref "U1") (pin "63") (pinfunction "PC7_63") (pintype "bidirectional"))
      (node (ref "U4") (pin "13") (pinfunction "CLK_13") (pintype "input"))
      (node (ref "U7") (pin "6") (pinfunction "CLK_6") (pintype "bidirectional"))
    )
    (net (code "88") (name "/SSP1_TXD") (class "Default")
      (node (ref "JP2") (pin "20") (pinfunction "20_20") (pintype "passive"))
      (node (ref "U1") (pin "61") (pinfunction "PC5_61") (pintype "bidirectional"))
      (node (ref "U4") (pin "1") (pinfunction "DIN_1") (pintype "input"))
      (node (ref "U7") (pin "5") (pinfunction "DI_5") (pintype "bidirectional"))
    )
    (net (code "89") (name "/SSP2_FSS") (class "Default")
      (node (ref "JP2") (pin "13") (pinfunction "13_13") (pintype "passive"))
      (node (ref "U1") (pin "68") (pinfunction "PC12_68") (pintype "bidirectional"))
    )
    (net (code "90") (name "/SSP2_RXD") (class "Default")
      (node (ref "JP2") (pin "19") (pinfunction "19_19") (pintype "passive"))
      (node (ref "U1") (pin "66") (pinfunction "PC10_66") (pintype "bidirectional"))
    )
    (net (code "91") (name "/SSP2_SCK") (class "Default")
      (node (ref "JP2") (pin "15") (pinfunction "15_15") (pintype "passive"))
      (node (ref "U1") (pin "67") (pinfunction "PC11_67") (pintype "bidirectional"))
    )
    (net (code "92") (name "/SSP2_TXD") (class "Default")
      (node (ref "JP2") (pin "17") (pinfunction "17_17") (pintype "passive"))
      (node (ref "U1") (pin "65") (pinfunction "PC9_65") (pintype "bidirectional"))
    )
    (net (code "93") (name "/STUSB_DM") (class "Default")
      (node (ref "R4") (pin "2") (pinfunction "2_2") (pintype "passive"))
      (node (ref "U3") (pin "32") (pinfunction "PA11_32") (pintype "bidirectional"))
    )
    (net (code "94") (name "/STUSB_DP") (class "Default")
      (node (ref "R5") (pin "2") (pinfunction "2_2") (pintype "passive"))
      (node (ref "U3") (pin "33") (pinfunction "PA12_33") (pintype "bidirectional"))
    )
    (net (code "95") (name "/ST_LED") (class "Default")
      (node (ref "R17") (pin "1") (pinfunction "1_1") (pintype "passive"))
      (node (ref "R18") (pin "1") (pinfunction "1_1") (pintype "passive"))
      (node (ref "U3") (pin "30") (pinfunction "PA9_30") (pintype "bidirectional"))
    )
    (net (code "96") (name "/SWCLK") (class "Default")
      (node (ref "JP3") (pin "1") (pinfunction "1_1") (pintype "passive"))
      (node (ref "U3") (pin "37") (pinfunction "PA14_37") (pintype "bidirectional"))
    )
    (net (code "97") (name "/SWDIO") (class "Default")
      (node (ref "JP3") (pin "2") (pinfunction "2_2") (pintype "passive"))
      (node (ref "U3") (pin "34") (pinfunction "PA13_34") (pintype "bidirectional"))
    )
    (net (code "98") (name "/T_JRST") (class "Default")
      (node (ref "R2") (pin "5") (pinfunction "P.5_5") (pintype "passive"))
      (node (ref "U1") (pin "142") (pinfunction "JTAG.RST_142") (pintype "bidirectional"))
      (node (ref "U3") (pin "19") (pinfunction "PB1_19") (pintype "bidirectional"))
    )
    (net (code "99") (name "/T_JTCK") (class "Default")
      (node (ref "R2") (pin "6") (pinfunction "P.6_6") (pintype "passive"))
      (node (ref "U1") (pin "141") (pinfunction "JTAG.TCK_141") (pintype "bidirectional"))
      (node (ref "U3") (pin "15") (pinfunction "PA5_15") (pintype "bidirectional"))
      (node (ref "U3") (pin "26") (pinfunction "PB13_26") (pintype "bidirectional"))
    )
    (net (code "100") (name "/T_JTDI") (class "Default")
      (node (ref "R2") (pin "7") (pinfunction "P.7_7") (pintype "passive"))
      (node (ref "U1") (pin "139") (pinfunction "JTAG.TDI_139") (pintype "bidirectional"))
      (node (ref "U3") (pin "17") (pinfunction "PA7_17") (pintype "bidirectional"))
    )
    (net (code "101") (name "/T_JTDO") (class "Default")
      (node (ref "U1") (pin "140") (pinfunction "JTAG.TDO_140") (pintype "bidirectional"))
      (node (ref "U3") (pin "16") (pinfunction "PA6_16") (pintype "bidirectional"))
    )
    (net (code "102") (name "/T_JTMS") (class "Default")
      (node (ref "R11") (pin "1") (pinfunction "1_1") (pintype "passive"))
      (node (ref "R2") (pin "8") (pinfunction "P.8_8") (pintype "passive"))
      (node (ref "U1") (pin "138") (pinfunction "JTAG.TMS_138") (pintype "bidirectional"))
      (node (ref "U3") (pin "27") (pinfunction "PB14_27") (pintype "bidirectional"))
    )
    (net (code "103") (name "/UART_CTS2") (class "Default")
      (node (ref "JP1") (pin "17") (pinfunction "17_17") (pintype "passive"))
      (node (ref "U1") (pin "50") (pinfunction "PD11_50") (pintype "bidirectional"))
      (node (ref "U8") (pin "9") (pinfunction "R2OUT_9") (pintype "output"))
    )
    (net (code "104") (name "/UART_RTS2") (class "Default")
      (node (ref "JP1") (pin "19") (pinfunction "19_19") (pintype "passive"))
      (node (ref "U1") (pin "49") (pinfunction "PD10_49") (pintype "bidirectional"))
      (node (ref "U8") (pin "10") (pinfunction "T2IN_10") (pintype "input"))
    )
    (net (code "105") (name "/UART_RX1") (class "Default")
      (node (ref "JP1") (pin "4") (pinfunction "4_4") (pintype "passive"))
      (node (ref "U1") (pin "102") (pinfunction "PC4_102") (pintype "bidirectional"))
    )
    (net (code "106") (name "/UART_RX2") (class "Default")
      (node (ref "JP1") (pin "13") (pinfunction "13_13") (pintype "passive"))
      (node (ref "U1") (pin "53") (pinfunction "PD14_53") (pintype "bidirectional"))
      (node (ref "U8") (pin "12") (pinfunction "R1OUT_12") (pintype "output"))
    )
    (net (code "107") (name "/UART_TX1") (class "Default")
      (node (ref "JP1") (pin "6") (pinfunction "6_6") (pintype "passive"))
      (node (ref "U1") (pin "101") (pinfunction "PC3_101") (pintype "bidirectional"))
    )
    (net (code "108") (name "/UART_TX2") (class "Default")
      (node (ref "JP1") (pin "15") (pinfunction "15_15") (pintype "passive"))
      (node (ref "U1") (pin "52") (pinfunction "PD13_52") (pintype "bidirectional"))
      (node (ref "U8") (pin "11") (pinfunction "T1IN_11") (pintype "input"))
    )
    (net (code "109") (name "/USB_DM") (class "Default")
      (node (ref "D1") (pin "6") (pinfunction "IO_1_6") (pintype "bidirectional"))
      (node (ref "U1") (pin "43") (pinfunction "USB.DN_43") (pintype "bidirectional"))
    )
    (net (code "110") (name "/USB_DP") (class "Default")
      (node (ref "D1") (pin "4") (pinfunction "IO_2_4") (pintype "bidirectional"))
      (node (ref "U1") (pin "42") (pinfunction "USB.DP_42") (pintype "bidirectional"))
    )
    (net (code "111") (name "/VDDA") (class "Default")
      (node (ref "C7") (pin "1") (pinfunction "1_1") (pintype "passive"))
      (node (ref "C8") (pin "1") (pinfunction "1_1") (pintype "passive"))
      (node (ref "L2") (pin "2") (pinfunction "2_2") (pintype "passive"))
      (node (ref "U1") (pin "10") (pinfunction "VDD2A_10") (pintype "bidirectional"))
      (node (ref "U1") (pin "14") (pinfunction "VDD3A_14") (pintype "bidirectional"))
      (node (ref "U1") (pin "16") (pinfunction "VDD4A_16") (pintype "bidirectional"))
      (node (ref "U1") (pin "45") (pinfunction "AUCC_45") (pintype "bidirectional"))
      (node (ref "U1") (pin "5") (pinfunction "VDD1A_5") (pintype "bidirectional"))
    )
    (net (code "112") (name "/WE") (class "Default")
      (node (ref "U1") (pin "98") (pinfunction "PC0_98") (pintype "bidirectional"))
      (node (ref "U2") (pin "17") (pinfunction "~{WE}_17") (pintype "input"))
    )
    (net (code "114") (name "/~{RESET}") (class "Default")
      (node (ref "C30") (pin "1") (pinfunction "1_1") (pintype "passive"))
      (node (ref "R10") (pin "1") (pinfunction "1_1") (pintype "passive"))
      (node (ref "S3") (pin "1") (pinfunction "S_1") (pintype "passive"))
      (node (ref "S3") (pin "2") (pinfunction "S1_2") (pintype "passive"))
      (node (ref "U1") (pin "60") (pinfunction "~{RESET}_60") (pintype "bidirectional"))
      (node (ref "U3") (pin "18") (pinfunction "PB0_18") (pintype "bidirectional"))
    )
    (net (code "115") (name "GND") (class "Default")
      (node (ref "C1") (pin "-") (pinfunction "-_-") (pintype "passive"))
      (node (ref "C10") (pin "2") (pinfunction "2_2") (pintype "passive"))
      (node (ref "C11") (pin "1") (pinfunction "1_1") (pintype "passive"))
      (node (ref "C12") (pin "1") (pinfunction "1_1") (pintype "passive"))
      (node (ref "C13") (pin "2") (pinfunction "2_2") (pintype "passive"))
      (node (ref "C14") (pin "2") (pinfunction "2_2") (pintype "passive"))
      (node (ref "C15") (pin "2") (pinfunction "2_2") (pintype "passive"))
      (node (ref "C16") (pin "1") (pinfunction "1_1") (pintype "passive"))
      (node (ref "C17") (pin "2") (pinfunction "2_2") (pintype "passive"))
      (node (ref "C18") (pin "1") (pinfunction "1_1") (pintype "passive"))
      (node (ref "C19") (pin "2") (pinfunction "2_2") (pintype "passive"))
      (node (ref "C2") (pin "2") (pinfunction "2_2") (pintype "passive"))
      (node (ref "C20") (pin "2") (pinfunction "2_2") (pintype "passive"))
      (node (ref "C21") (pin "2") (pinfunction "2_2") (pintype "passive"))
      (node (ref "C24") (pin "2") (pinfunction "2_2") (pintype "passive"))
      (node (ref "C25") (pin "2") (pinfunction "2_2") (pintype "passive"))
      (node (ref "C28") (pin "2") (pinfunction "2_2") (pintype "passive"))
      (node (ref "C29") (pin "1") (pinfunction "1_1") (pintype "passive"))
      (node (ref "C3") (pin "-") (pinfunction "-_-") (pintype "passive"))
      (node (ref "C30") (pin "2") (pinfunction "2_2") (pintype "passive"))
      (node (ref "C4") (pin "2") (pinfunction "2_2") (pintype "passive"))
      (node (ref "C5") (pin "2") (pinfunction "2_2") (pintype "passive"))
      (node (ref "C6") (pin "2") (pinfunction "2_2") (pintype "passive"))
      (node (ref "C7") (pin "2") (pinfunction "2_2") (pintype "passive"))
      (node (ref "C8") (pin "2") (pinfunction "2_2") (pintype "passive"))
      (node (ref "C9") (pin "-") (pinfunction "-_-") (pintype "passive"))
      (node (ref "D1") (pin "2") (pinfunction "GND_2") (pintype "power_in"))
      (node (ref "D10") (pin "C") (pinfunction "C_C") (pintype "passive"))
      (node (ref "D5") (pin "C") (pinfunction "C_C") (pintype "passive"))
      (node (ref "D6") (pin "C") (pinfunction "C_C") (pintype "passive"))
      (node (ref "D7") (pin "C") (pinfunction "C_C") (pintype "passive"))
      (node (ref "D8") (pin "C") (pinfunction "C_C") (pintype "passive"))
      (node (ref "D9") (pin "C") (pinfunction "C_C") (pintype "passive"))
      (node (ref "J1") (pin "4_GND") (pinfunction "GND_4_GND") (pintype "power_in"))
      (node (ref "J1") (pin "M1") (pinfunction "SHLD_M1") (pintype "power_in"))
      (node (ref "J1") (pin "M2") (pinfunction "SHLD_M2") (pintype "power_in"))
      (node (ref "J2") (pin "4_GND") (pinfunction "GND_4_GND") (pintype "power_in"))
      (node (ref "J2") (pin "M1") (pinfunction "SHLD_M1") (pintype "power_in"))
      (node (ref "J2") (pin "M2") (pinfunction "SHLD_M2") (pintype "power_in"))
      (node (ref "JP1") (pin "2") (pinfunction "2_2") (pintype "passive"))
      (node (ref "JP2") (pin "2") (pinfunction "2_2") (pintype "passive"))
      (node (ref "JP3") (pin "3") (pinfunction "3_3") (pintype "passive"))
      (node (ref "R1") (pin "1") (pinfunction "P.1_1") (pintype "passive"))
      (node (ref "R1") (pin "2") (pinfunction "P.2_2") (pintype "passive"))
      (node (ref "R1") (pin "3") (pinfunction "P.3_3") (pintype "passive"))
      (node (ref "R1") (pin "4") (pinfunction "P.4_4") (pintype "passive"))
      (node (ref "R14") (pin "1") (pinfunction "1_1") (pintype "passive"))
      (node (ref "R16") (pin "2") (pinfunction "2_2") (pintype "passive"))
      (node (ref "R19") (pin "2") (pinfunction "2_2") (pintype "passive"))
      (node (ref "R20") (pin "2") (pinfunction "2_2") (pintype "passive"))
      (node (ref "R22") (pin "2") (pinfunction "2_2") (pintype "passive"))
      (node (ref "R29") (pin "2") (pinfunction "2_2") (pintype "passive"))
      (node (ref "R38") (pin "1") (pinfunction "1_1") (pintype "passive"))
      (node (ref "R40") (pin "1") (pinfunction "1_1") (pintype "passive"))
      (node (ref "R7") (pin "1") (pinfunction "1_1") (pintype "passive"))
      (node (ref "S3") (pin "3") (pinfunction "P_3") (pintype "passive"))
      (node (ref "S3") (pin "4") (pinfunction "P1_4") (pintype "passive"))
      (node (ref "U1") (pin "1") (pinfunction "VSS1A_1") (pintype "bidirectional"))
      (node (ref "U1") (pin "11") (pinfunction "VSS2A_11") (pintype "bidirectional"))
      (node (ref "U1") (pin "125") (pinfunction "GND_125") (pintype "bidirectional"))
      (node (ref "U1") (pin "13") (pinfunction "VSS3A_13") (pintype "bidirectional"))
      (node (ref "U1") (pin "15") (pinfunction "VSS4A_15") (pintype "bidirectional"))
      (node (ref "U1") (pin "32") (pinfunction "GND_32") (pintype "bidirectional"))
      (node (ref "U1") (pin "35") (pinfunction "JTAG.EN_35") (pintype "bidirectional"))
      (node (ref "U1") (pin "4") (pinfunction "VSS1A_4") (pintype "bidirectional"))
      (node (ref "U1") (pin "44") (pinfunction "AGND_44") (pintype "bidirectional"))
      (node (ref "U1") (pin "75") (pinfunction "GND_75") (pintype "bidirectional"))
      (node (ref "U2") (pin "12") (pinfunction "GND_12") (pintype "power_in"))
      (node (ref "U2") (pin "34") (pinfunction "GND_34") (pintype "power_in"))
      (node (ref "U3") (pin "20") (pinfunction "PB2_20") (pintype "bidirectional"))
      (node (ref "U3") (pin "23") (pinfunction "VSS_1_23") (pintype "bidirectional"))
      (node (ref "U3") (pin "35") (pinfunction "VSS_2_35") (pintype "bidirectional"))
      (node (ref "U3") (pin "47") (pinfunction "VSS_3_47") (pintype "bidirectional"))
      (node (ref "U3") (pin "8") (pinfunction "VSSA_8") (pintype "bidirectional"))
      (node (ref "U4") (pin "4") (pinfunction "GND_4") (pintype "power_in"))
      (node (ref "U4") (pin "9") (pinfunction "GND_9") (pintype "power_in"))
      (node (ref "U5") (pin "1") (pinfunction "GND_1") (pintype "input"))
      (node (ref "U6") (pin "2") (pinfunction "VSS_2") (pintype "bidirectional"))
      (node (ref "U7") (pin "4") (pinfunction "GND_4") (pintype "bidirectional"))
      (node (ref "U8") (pin "15") (pinfunction "GND_15") (pintype "power_in"))
      (node (ref "X1") (pin "5") (pinfunction "5_5") (pintype "passive"))
      (node (ref "X1") (pin "6") (pinfunction "6_6") (pintype "passive"))
      (node (ref "X2") (pin "3") (pinfunction "3_3") (pintype "passive"))
      (node (ref "X2") (pin "6") (pinfunction "6_6") (pintype "passive"))
      (node (ref "X3") (pin "P10") (pinfunction "GLED-_P10") (pintype "passive"))
      (node (ref "X3") (pin "P11") (pinfunction "YLED-_P11") (pintype "passive"))
      (node (ref "X3") (pin "P8") (pinfunction "CGND_P8") (pintype "passive"))
      (node (ref "X3") (pin "SHIELD1") (pinfunction "S1_SHIELD1") (pintype "passive"))
      (node (ref "X3") (pin "SHIELD2") (pinfunction "S2_SHIELD2") (pintype "passive"))
      (node (ref "Y2") (pin "2") (pinfunction "2_2") (pintype "bidirectional"))
      (node (ref "Y2") (pin "4") (pinfunction "4_4") (pintype "bidirectional"))
      (node (ref "Y3") (pin "2") (pinfunction "2_2") (pintype "bidirectional"))
      (node (ref "Y3") (pin "4") (pinfunction "4_4") (pintype "bidirectional"))
    )
    (net (code "116") (name "Net-(C3-Pad+)") (class "Default")
      (node (ref "C3") (pin "+") (pinfunction "+_+") (pintype "passive"))
      (node (ref "L1") (pin "1") (pinfunction "1_1") (pintype "passive"))
      (node (ref "U5") (pin "2") (pinfunction "OUT_2") (pintype "passive"))
      (node (ref "U5") (pin "4") (pinfunction "OUT_4") (pintype "passive"))
    )
    (net (code "117") (name "Net-(D1-IO.1)") (class "Default")
      (node (ref "D1") (pin "1") (pinfunction "IO.1_1") (pintype "bidirectional"))
      (node (ref "J1") (pin "2_DM") (pinfunction "D-_2_DM") (pintype "bidirectional"))
    )
    (net (code "118") (name "Net-(D1-IO.2)") (class "Default")
      (node (ref "D1") (pin "3") (pinfunction "IO.2_3") (pintype "bidirectional"))
      (node (ref "J1") (pin "3_DP") (pinfunction "D+_3_DP") (pintype "bidirectional"))
    )
    (net (code "119") (name "Net-(D2-PadA)") (class "Default")
      (node (ref "D2") (pin "A") (pinfunction "A_A") (pintype "passive"))
      (node (ref "F1") (pin "2") (pinfunction "2_2") (pintype "passive"))
    )
    (net (code "120") (name "Net-(D3-PadA)") (class "Default")
      (node (ref "D3") (pin "A") (pinfunction "A_A") (pintype "passive"))
      (node (ref "F2") (pin "2") (pinfunction "2_2") (pintype "passive"))
    )
    (net (code "121") (name "Net-(D5-PadA)") (class "Default")
      (node (ref "D5") (pin "A") (pinfunction "A_A") (pintype "passive"))
      (node (ref "R24") (pin "2") (pinfunction "2_2") (pintype "passive"))
    )
    (net (code "122") (name "Net-(D6-PadA)") (class "Default")
      (node (ref "D6") (pin "A") (pinfunction "A_A") (pintype "passive"))
      (node (ref "R25") (pin "2") (pinfunction "2_2") (pintype "passive"))
    )
    (net (code "123") (name "Net-(D7-PadA)") (class "Default")
      (node (ref "D7") (pin "A") (pinfunction "A_A") (pintype "passive"))
      (node (ref "R26") (pin "2") (pinfunction "2_2") (pintype "passive"))
    )
    (net (code "124") (name "Net-(D8-PadA)") (class "Default")
      (node (ref "D8") (pin "A") (pinfunction "A_A") (pintype "passive"))
      (node (ref "R27") (pin "2") (pinfunction "2_2") (pintype "passive"))
    )
    (net (code "125") (name "Net-(D9-PadA)") (class "Default")
      (node (ref "D9") (pin "A") (pinfunction "A_A") (pintype "passive"))
      (node (ref "R28") (pin "2") (pinfunction "2_2") (pintype "passive"))
    )
    (net (code "126") (name "Net-(D10-PadA)") (class "Default")
      (node (ref "D10") (pin "A") (pinfunction "A_A") (pintype "passive"))
      (node (ref "R18") (pin "2") (pinfunction "2_2") (pintype "passive"))
    )
    (net (code "127") (name "Net-(D11-PadC)") (class "Default")
      (node (ref "D11") (pin "C") (pinfunction "C_C") (pintype "passive"))
      (node (ref "R17") (pin "2") (pinfunction "2_2") (pintype "passive"))
    )
    (net (code "128") (name "Net-(DS1-A)") (class "Default")
      (node (ref "DS1") (pin "1") (pinfunction "A_1") (pintype "bidirectional"))
      (node (ref "U4") (pin "14") (pinfunction "SEGA_14") (pintype "output"))
    )
    (net (code "129") (name "Net-(DS1-B)") (class "Default")
      (node (ref "DS1") (pin "2") (pinfunction "B_2") (pintype "bidirectional"))
      (node (ref "U4") (pin "16") (pinfunction "SEGB_16") (pintype "output"))
    )
    (net (code "130") (name "Net-(DS1-C)") (class "Default")
      (node (ref "DS1") (pin "3") (pinfunction "C_3") (pintype "bidirectional"))
      (node (ref "U4") (pin "20") (pinfunction "SEGC_20") (pintype "output"))
    )
    (net (code "131") (name "Net-(DS1-D)") (class "Default")
      (node (ref "DS1") (pin "4") (pinfunction "D_4") (pintype "bidirectional"))
      (node (ref "U4") (pin "23") (pinfunction "SEGD_23") (pintype "output"))
    )
    (net (code "132") (name "Net-(DS1-D1)") (class "Default")
      (node (ref "DS1") (pin "8") (pinfunction "D1_8") (pintype "bidirectional"))
      (node (ref "U4") (pin "2") (pinfunction "DIG0_2") (pintype "open_collector"))
    )
    (net (code "133") (name "Net-(DS1-D2)") (class "Default")
      (node (ref "DS1") (pin "9") (pinfunction "D2_9") (pintype "bidirectional"))
      (node (ref "U4") (pin "11") (pinfunction "DIG1_11") (pintype "open_collector"))
    )
    (net (code "134") (name "Net-(DS1-D3)") (class "Default")
      (node (ref "DS1") (pin "10") (pinfunction "D3_10") (pintype "bidirectional"))
      (node (ref "U4") (pin "6") (pinfunction "DIG2_6") (pintype "open_collector"))
    )
    (net (code "135") (name "Net-(DS1-D4)") (class "Default")
      (node (ref "DS1") (pin "11") (pinfunction "D4_11") (pintype "bidirectional"))
      (node (ref "U4") (pin "7") (pinfunction "DIG3_7") (pintype "open_collector"))
    )
    (net (code "136") (name "Net-(DS1-D5)") (class "Default")
      (node (ref "DS1") (pin "12") (pinfunction "D5_12") (pintype "bidirectional"))
      (node (ref "U4") (pin "3") (pinfunction "DIG4_3") (pintype "open_collector"))
    )
    (net (code "137") (name "Net-(DS1-E)") (class "Default")
      (node (ref "DS1") (pin "5") (pinfunction "E_5") (pintype "bidirectional"))
      (node (ref "U4") (pin "21") (pinfunction "SEGE_21") (pintype "output"))
    )
    (net (code "138") (name "Net-(DS1-F)") (class "Default")
      (node (ref "DS1") (pin "6") (pinfunction "F_6") (pintype "bidirectional"))
      (node (ref "U4") (pin "15") (pinfunction "SEGF_15") (pintype "output"))
    )
    (net (code "139") (name "Net-(DS1-G)") (class "Default")
      (node (ref "DS1") (pin "7") (pinfunction "G_7") (pintype "bidirectional"))
      (node (ref "U4") (pin "17") (pinfunction "SEGG_17") (pintype "output"))
    )
    (net (code "140") (name "Net-(J1-VBUS)") (class "Default")
      (node (ref "F1") (pin "1") (pinfunction "1_1") (pintype "passive"))
      (node (ref "J1") (pin "1_VBUS") (pinfunction "VBUS_1_VBUS") (pintype "power_in"))
    )
    (net (code "141") (name "Net-(J2-D+)") (class "Default")
      (node (ref "J2") (pin "3_DP") (pinfunction "D+_3_DP") (pintype "bidirectional"))
      (node (ref "R3") (pin "2") (pinfunction "2_2") (pintype "passive"))
      (node (ref "R5") (pin "1") (pinfunction "1_1") (pintype "passive"))
    )
    (net (code "142") (name "Net-(J2-D-)") (class "Default")
      (node (ref "J2") (pin "2_DM") (pinfunction "D-_2_DM") (pintype "bidirectional"))
      (node (ref "R4") (pin "1") (pinfunction "1_1") (pintype "passive"))
    )
    (net (code "143") (name "Net-(J2-VBUS)") (class "Default")
      (node (ref "F2") (pin "1") (pinfunction "1_1") (pintype "passive"))
      (node (ref "J2") (pin "1_VBUS") (pinfunction "VBUS_1_VBUS") (pintype "power_in"))
    )
    (net (code "144") (name "Net-(R23-Pad2)") (class "Default")
      (node (ref "R23") (pin "2") (pinfunction "2_2") (pintype "passive"))
      (node (ref "SJ1") (pin "1") (pinfunction "1_1") (pintype "passive"))
    )
    (net (code "145") (name "Net-(S1-P)") (class "Default")
      (node (ref "R37") (pin "2") (pinfunction "2_2") (pintype "passive"))
      (node (ref "R38") (pin "2") (pinfunction "2_2") (pintype "passive"))
      (node (ref "S1") (pin "3") (pinfunction "P_3") (pintype "passive"))
      (node (ref "S1") (pin "4") (pinfunction "P1_4") (pintype "passive"))
    )
    (net (code "146") (name "Net-(S2-P)") (class "Default")
      (node (ref "R39") (pin "2") (pinfunction "2_2") (pintype "passive"))
      (node (ref "R40") (pin "2") (pinfunction "2_2") (pintype "passive"))
      (node (ref "S2") (pin "3") (pinfunction "P_3") (pintype "passive"))
      (node (ref "S2") (pin "4") (pinfunction "P1_4") (pintype "passive"))
    )
    (net (code "147") (name "Net-(U1D-EXRES1)") (class "Default")
      (node (ref "R7") (pin "2") (pinfunction "2_2") (pintype "passive"))
      (node (ref "U1") (pin "12") (pinfunction "EXRES1_12") (pintype "bidirectional"))
    )
    (net (code "148") (name "Net-(U1D-ITCMLAEN)") (class "Default")
      (node (ref "R9") (pin "2") (pinfunction "2_2") (pintype "passive"))
      (node (ref "U1") (pin "17") (pinfunction "ITCMLAEN_17") (pintype "bidirectional"))
    )
    (net (code "149") (name "Net-(U1D-WAKEUP)") (class "Default")
      (node (ref "R8") (pin "2") (pinfunction "2_2") (pintype "passive"))
      (node (ref "U1") (pin "39") (pinfunction "WAKEUP_39") (pintype "bidirectional"))
    )
    (net (code "150") (name "Net-(U2-~{LB})") (class "Default")
      (node (ref "R20") (pin "1") (pinfunction "1_1") (pintype "passive"))
      (node (ref "U2") (pin "39") (pinfunction "~{LB}_39") (pintype "input"))
      (node (ref "U2") (pin "40") (pinfunction "~{UB}_40") (pintype "input"))
    )
    (net (code "151") (name "Net-(U3-BOOT0)") (class "Default")
      (node (ref "R19") (pin "1") (pinfunction "1_1") (pintype "passive"))
      (node (ref "U3") (pin "44") (pinfunction "BOOT0_44") (pintype "bidirectional"))
    )
    (net (code "152") (name "Net-(U3-NRST)") (class "Default")
      (node (ref "C13") (pin "1") (pinfunction "1_1") (pintype "passive"))
      (node (ref "R15") (pin "2") (pinfunction "2_2") (pintype "passive"))
      (node (ref "U3") (pin "7") (pinfunction "NRST_7") (pintype "bidirectional"))
    )
    (net (code "153") (name "Net-(U3-PB5)") (class "Default")
      (node (ref "R12") (pin "1") (pinfunction "1_1") (pintype "passive"))
      (node (ref "U3") (pin "41") (pinfunction "PB5_41") (pintype "bidirectional"))
    )
    (net (code "154") (name "Net-(U3-PB6)") (class "Default")
      (node (ref "R12") (pin "2") (pinfunction "2_2") (pintype "passive"))
      (node (ref "U3") (pin "42") (pinfunction "PB6_42") (pintype "bidirectional"))
    )
    (net (code "155") (name "Net-(U3-PB12)") (class "Default")
      (node (ref "R11") (pin "2") (pinfunction "2_2") (pintype "passive"))
      (node (ref "U3") (pin "25") (pinfunction "PB12_25") (pintype "bidirectional"))
    )
    (net (code "156") (name "Net-(U3-PC13-TAMPER-RTC)") (class "Default")
      (node (ref "R16") (pin "1") (pinfunction "1_1") (pintype "passive"))
      (node (ref "U3") (pin "2") (pinfunction "PC13-TAMPER-RTC_2") (pintype "bidirectional"))
    )
    (net (code "157") (name "Net-(U3-PD0_OSC_IN)") (class "Default")
      (node (ref "C12") (pin "2") (pinfunction "2_2") (pintype "passive"))
      (node (ref "U3") (pin "5") (pinfunction "PD0_OSC_IN_5") (pintype "bidirectional"))
      (node (ref "Y4") (pin "2") (pinfunction "2_2") (pintype "passive"))
    )
    (net (code "158") (name "Net-(U3-PD1-OSC_OUT)") (class "Default")
      (node (ref "C11") (pin "2") (pinfunction "2_2") (pintype "passive"))
      (node (ref "U3") (pin "6") (pinfunction "PD1-OSC_OUT_6") (pintype "bidirectional"))
      (node (ref "Y4") (pin "1") (pinfunction "1_1") (pintype "passive"))
    )
    (net (code "159") (name "Net-(U4-ISET)") (class "Default")
      (node (ref "R21") (pin "2") (pinfunction "2_2") (pintype "passive"))
      (node (ref "U4") (pin "18") (pinfunction "ISET_18") (pintype "input"))
    )
    (net (code "160") (name "Net-(U6-RS)") (class "Default")
      (node (ref "R22") (pin "1") (pinfunction "1_1") (pintype "passive"))
      (node (ref "U6") (pin "8") (pinfunction "RS_8") (pintype "bidirectional"))
    )
    (net (code "161") (name "Net-(U8A-C1+)") (class "Default")
      (node (ref "C22") (pin "2") (pinfunction "2_2") (pintype "passive"))
      (node (ref "U8") (pin "1") (pinfunction "C1+_1") (pintype "bidirectional"))
    )
    (net (code "162") (name "Net-(U8A-C1-)") (class "Default")
      (node (ref "C22") (pin "1") (pinfunction "1_1") (pintype "passive"))
      (node (ref "U8") (pin "3") (pinfunction "C1-_3") (pintype "bidirectional"))
    )
    (net (code "163") (name "Net-(U8A-C2+)") (class "Default")
      (node (ref "C23") (pin "2") (pinfunction "2_2") (pintype "passive"))
      (node (ref "U8") (pin "4") (pinfunction "C2+_4") (pintype "bidirectional"))
    )
    (net (code "164") (name "Net-(U8A-C2-)") (class "Default")
      (node (ref "C23") (pin "1") (pinfunction "1_1") (pintype "passive"))
      (node (ref "U8") (pin "5") (pinfunction "C2-_5") (pintype "bidirectional"))
    )
    (net (code "165") (name "Net-(U8A-V+)") (class "Default")
      (node (ref "C24") (pin "1") (pinfunction "1_1") (pintype "passive"))
      (node (ref "U8") (pin "2") (pinfunction "V+_2") (pintype "bidirectional"))
    )
    (net (code "166") (name "Net-(U8A-V-)") (class "Default")
      (node (ref "C25") (pin "1") (pinfunction "1_1") (pintype "passive"))
      (node (ref "U8") (pin "6") (pinfunction "V-_6") (pintype "bidirectional"))
    )
    (net (code "167") (name "Net-(X3-GLED+)") (class "Default")
      (node (ref "R35") (pin "2") (pinfunction "2_2") (pintype "passive"))
      (node (ref "X3") (pin "P9") (pinfunction "GLED+_P9") (pintype "passive"))
    )
    (net (code "168") (name "Net-(X3-RD+)") (class "Default")
      (node (ref "C26") (pin "2") (pinfunction "2_2") (pintype "passive"))
      (node (ref "X3") (pin "P3") (pinfunction "RD+_P3") (pintype "passive"))
    )
    (net (code "169") (name "Net-(X3-RD-)") (class "Default")
      (node (ref "C27") (pin "2") (pinfunction "2_2") (pintype "passive"))
      (node (ref "X3") (pin "P6") (pinfunction "RD-_P6") (pintype "passive"))
    )
    (net (code "170") (name "Net-(X3-TCT)") (class "Default")
      (node (ref "C29") (pin "2") (pinfunction "2_2") (pintype "passive"))
      (node (ref "R34") (pin "1") (pinfunction "1_1") (pintype "passive"))
      (node (ref "X3") (pin "P4") (pinfunction "TCT_P4") (pintype "passive"))
    )
    (net (code "171") (name "Net-(X3-YLED+)") (class "Default")
      (node (ref "R36") (pin "2") (pinfunction "2_2") (pintype "passive"))
      (node (ref "X3") (pin "P12") (pinfunction "YLED+_P12") (pintype "passive"))
    )
    (net (code "172") (name "VBUS") (class "Default")
      (node (ref "C1") (pin "+") (pinfunction "+_+") (pintype "passive"))
      (node (ref "C2") (pin "1") (pinfunction "1_1") (pintype "passive"))
      (node (ref "D1") (pin "5") (pinfunction "VBUS_5") (pintype "bidirectional"))
      (node (ref "D2") (pin "C") (pinfunction "C_C") (pintype "passive"))
      (node (ref "D3") (pin "C") (pinfunction "C_C") (pintype "passive"))
      (node (ref "D4") (pin "A") (pinfunction "A_A") (pintype "passive"))
      (node (ref "U5") (pin "3") (pinfunction "IN_3") (pintype "input"))
      (node (ref "U6") (pin "3") (pinfunction "VDD_3") (pintype "bidirectional"))
    )
    (net (code "173") (name "unconnected-(R1-P.5-Pad5)") (class "Default")
      (node (ref "R1") (pin "5") (pinfunction "P.5_5") (pintype "passive"))
    )
    (net (code "174") (name "unconnected-(U1A-PB7-Pad111)") (class "Default")
      (node (ref "U1") (pin "111") (pinfunction "PB7_111") (pintype "bidirectional"))
    )
    (net (code "175") (name "unconnected-(U1A-PB8-Pad110)") (class "Default")
      (node (ref "U1") (pin "110") (pinfunction "PB8_110") (pintype "bidirectional"))
    )
    (net (code "176") (name "unconnected-(U1A-PB9-Pad109)") (class "Default")
      (node (ref "U1") (pin "109") (pinfunction "PB9_109") (pintype "bidirectional"))
    )
    (net (code "177") (name "unconnected-(U1A-PB12-Pad106)") (class "Default")
      (node (ref "U1") (pin "106") (pinfunction "PB12_106") (pintype "bidirectional"))
    )
    (net (code "178") (name "unconnected-(U1A-PB13-Pad105)") (class "Default")
      (node (ref "U1") (pin "105") (pinfunction "PB13_105") (pintype "bidirectional"))
    )
    (net (code "179") (name "unconnected-(U1A-PB14-Pad104)") (class "Default")
      (node (ref "U1") (pin "104") (pinfunction "PB14_104") (pintype "bidirectional"))
    )
    (net (code "180") (name "unconnected-(U1A-PB15-Pad103)") (class "Default")
      (node (ref "U1") (pin "103") (pinfunction "PB15_103") (pintype "bidirectional"))
    )
    (net (code "181") (name "unconnected-(U1B-PC15-Pad74)") (class "Default")
      (node (ref "U1") (pin "74") (pinfunction "PC15_74") (pintype "bidirectional"))
    )
    (net (code "182") (name "unconnected-(U1B-PD4-Pad85)") (class "Default")
      (node (ref "U1") (pin "85") (pinfunction "PD4_85") (pintype "bidirectional"))
    )
    (net (code "183") (name "unconnected-(U1B-PD5-Pad86)") (class "Default")
      (node (ref "U1") (pin "86") (pinfunction "PD5_86") (pintype "bidirectional"))
    )
    (net (code "184") (name "unconnected-(U1B-PD6-Pad87)") (class "Default")
      (node (ref "U1") (pin "87") (pinfunction "PD6_87") (pintype "bidirectional"))
    )
    (net (code "185") (name "unconnected-(U1B-PD7-Pad46)") (class "Default")
      (node (ref "U1") (pin "46") (pinfunction "PD7_46") (pintype "bidirectional"))
    )
    (net (code "186") (name "unconnected-(U1B-PD8-Pad47)") (class "Default")
      (node (ref "U1") (pin "47") (pinfunction "PD8_47") (pintype "bidirectional"))
    )
    (net (code "187") (name "unconnected-(U1B-PD12-Pad51)") (class "Default")
      (node (ref "U1") (pin "51") (pinfunction "PD12_51") (pintype "bidirectional"))
    )
    (net (code "188") (name "unconnected-(U1B-PD15-Pad54)") (class "Default")
      (node (ref "U1") (pin "54") (pinfunction "PD15_54") (pintype "bidirectional"))
    )
    (net (code "189") (name "unconnected-(U1C-PE0-Pad55)") (class "Default")
      (node (ref "U1") (pin "55") (pinfunction "PE0_55") (pintype "bidirectional"))
    )
    (net (code "190") (name "unconnected-(U1C-PE1-Pad56)") (class "Default")
      (node (ref "U1") (pin "56") (pinfunction "PE1_56") (pintype "bidirectional"))
    )
    (net (code "191") (name "unconnected-(U1C-PE5-Pad20)") (class "Default")
      (node (ref "U1") (pin "20") (pinfunction "PE5_20") (pintype "bidirectional"))
    )
    (net (code "192") (name "unconnected-(U1C-PE8-Pad21)") (class "Default")
      (node (ref "U1") (pin "21") (pinfunction "PE8_21") (pintype "bidirectional"))
    )
    (net (code "193") (name "unconnected-(U1C-PE15-Pad28)") (class "Default")
      (node (ref "U1") (pin "28") (pinfunction "PE15_28") (pintype "bidirectional"))
    )
    (net (code "194") (name "unconnected-(U1C-PF2-Pad31)") (class "Default")
      (node (ref "U1") (pin "31") (pinfunction "PF2_31") (pintype "bidirectional"))
    )
    (net (code "195") (name "unconnected-(U1D-EXT.POR-Pad41)") (class "Default")
      (node (ref "U1") (pin "41") (pinfunction "EXT.POR_41") (pintype "bidirectional"))
    )
    (net (code "196") (name "unconnected-(U1D-NC-Pad143)") (class "Default")
      (node (ref "U1") (pin "143") (pinfunction "NC_143") (pintype "bidirectional"))
    )
    (net (code "197") (name "unconnected-(U1D-NC-Pad144)") (class "Default")
      (node (ref "U1") (pin "144") (pinfunction "NC_144") (pintype "bidirectional"))
    )
    (net (code "198") (name "unconnected-(U1D-RST.BYP-Pad126)") (class "Default")
      (node (ref "U1") (pin "126") (pinfunction "RST.BYP_126") (pintype "bidirectional"))
    )
    (net (code "199") (name "unconnected-(U1D-SHDN-Pad40)") (class "Default")
      (node (ref "U1") (pin "40") (pinfunction "SHDN_40") (pintype "bidirectional"))
    )
    (net (code "200") (name "unconnected-(U1D-TM0-Pad79)") (class "Default")
      (node (ref "U1") (pin "79") (pinfunction "TM0_79") (pintype "bidirectional"))
    )
    (net (code "201") (name "unconnected-(U1D-TM1-Pad78)") (class "Default")
      (node (ref "U1") (pin "78") (pinfunction "TM1_78") (pintype "bidirectional"))
    )
    (net (code "202") (name "unconnected-(U1D-TM2-Pad80)") (class "Default")
      (node (ref "U1") (pin "80") (pinfunction "TM2_80") (pintype "bidirectional"))
    )
    (net (code "203") (name "unconnected-(U1D-TSTBUSA-Pad9)") (class "Default")
      (node (ref "U1") (pin "9") (pinfunction "TSTBUSA_9") (pintype "bidirectional"))
    )
    (net (code "204") (name "unconnected-(U1D-VDD-Pad36)") (class "Default")
      (node (ref "U1") (pin "36") (pinfunction "VDD_36") (pintype "bidirectional"))
    )
    (net (code "205") (name "unconnected-(U1D-VPP-Pad77)") (class "Default")
      (node (ref "U1") (pin "77") (pinfunction "VPP_77") (pintype "bidirectional"))
    )
    (net (code "206") (name "unconnected-(U3-PA1-Pad11)") (class "Default")
      (node (ref "U3") (pin "11") (pinfunction "PA1_11") (pintype "bidirectional"))
    )
    (net (code "207") (name "unconnected-(U3-PA2-Pad12)") (class "Default")
      (node (ref "U3") (pin "12") (pinfunction "PA2_12") (pintype "bidirectional"))
    )
    (net (code "208") (name "unconnected-(U3-PA3-Pad13)") (class "Default")
      (node (ref "U3") (pin "13") (pinfunction "PA3_13") (pintype "bidirectional"))
    )
    (net (code "209") (name "unconnected-(U3-PA4-Pad14)") (class "Default")
      (node (ref "U3") (pin "14") (pinfunction "PA4_14") (pintype "bidirectional"))
    )
    (net (code "210") (name "unconnected-(U3-PA8-Pad29)") (class "Default")
      (node (ref "U3") (pin "29") (pinfunction "PA8_29") (pintype "bidirectional"))
    )
    (net (code "211") (name "unconnected-(U3-PA10-Pad31)") (class "Default")
      (node (ref "U3") (pin "31") (pinfunction "PA10_31") (pintype "bidirectional"))
    )
    (net (code "212") (name "unconnected-(U3-PA15-Pad38)") (class "Default")
      (node (ref "U3") (pin "38") (pinfunction "PA15_38") (pintype "bidirectional"))
    )
    (net (code "213") (name "unconnected-(U3-PB3-Pad39)") (class "Default")
      (node (ref "U3") (pin "39") (pinfunction "PB3_39") (pintype "bidirectional"))
    )
    (net (code "214") (name "unconnected-(U3-PB4-Pad40)") (class "Default")
      (node (ref "U3") (pin "40") (pinfunction "PB4_40") (pintype "bidirectional"))
    )
    (net (code "215") (name "unconnected-(U3-PB7-Pad43)") (class "Default")
      (node (ref "U3") (pin "43") (pinfunction "PB7_43") (pintype "bidirectional"))
    )
    (net (code "216") (name "unconnected-(U3-PB8-Pad45)") (class "Default")
      (node (ref "U3") (pin "45") (pinfunction "PB8_45") (pintype "bidirectional"))
    )
    (net (code "217") (name "unconnected-(U3-PB9-Pad46)") (class "Default")
      (node (ref "U3") (pin "46") (pinfunction "PB9_46") (pintype "bidirectional"))
    )
    (net (code "218") (name "unconnected-(U3-PB10-Pad21)") (class "Default")
      (node (ref "U3") (pin "21") (pinfunction "PB10_21") (pintype "bidirectional"))
    )
    (net (code "219") (name "unconnected-(U3-PB11-Pad22)") (class "Default")
      (node (ref "U3") (pin "22") (pinfunction "PB11_22") (pintype "bidirectional"))
    )
    (net (code "220") (name "unconnected-(U3-PB15-Pad28)") (class "Default")
      (node (ref "U3") (pin "28") (pinfunction "PB15_28") (pintype "bidirectional"))
    )
    (net (code "221") (name "unconnected-(U3-PC14-OSC32_IN-Pad3)") (class "Default")
      (node (ref "U3") (pin "3") (pinfunction "PC14-OSC32_IN_3") (pintype "bidirectional"))
    )
    (net (code "222") (name "unconnected-(U3-PC15-OSC32_OUT-Pad4)") (class "Default")
      (node (ref "U3") (pin "4") (pinfunction "PC15-OSC32_OUT_4") (pintype "bidirectional"))
    )
    (net (code "223") (name "unconnected-(U4-DIG5-Pad10)") (class "Default")
      (node (ref "U4") (pin "10") (pinfunction "DIG5_10") (pintype "open_collector"))
    )
    (net (code "224") (name "unconnected-(U4-DIG6-Pad5)") (class "Default")
      (node (ref "U4") (pin "5") (pinfunction "DIG6_5") (pintype "open_collector"))
    )
    (net (code "225") (name "unconnected-(U4-DIG7-Pad8)") (class "Default")
      (node (ref "U4") (pin "8") (pinfunction "DIG7_8") (pintype "open_collector"))
    )
    (net (code "226") (name "unconnected-(U4-DOUT-Pad24)") (class "Default")
      (node (ref "U4") (pin "24") (pinfunction "DOUT_24") (pintype "output"))
    )
    (net (code "227") (name "unconnected-(U4-SEGDP-Pad22)") (class "Default")
      (node (ref "U4") (pin "22") (pinfunction "SEGDP_22") (pintype "output"))
    )
    (net (code "228") (name "unconnected-(U6-VREF-Pad5)") (class "Default")
      (node (ref "U6") (pin "5") (pinfunction "VREF_5") (pintype "bidirectional"))
    )
    (net (code "229") (name "unconnected-(X1-Pad1)") (class "Default")
      (node (ref "X1") (pin "1") (pinfunction "1_1") (pintype "passive"))
    )
    (net (code "230") (name "unconnected-(X1-Pad4)") (class "Default")
      (node (ref "X1") (pin "4") (pinfunction "4_4") (pintype "passive"))
    )
    (net (code "231") (name "unconnected-(X1-Pad9)") (class "Default")
      (node (ref "X1") (pin "9") (pinfunction "9_9") (pintype "passive"))
    )
    (net (code "232") (name "unconnected-(X1-PadG1)") (class "Default")
      (node (ref "X1") (pin "G1") (pinfunction "G1_G1") (pintype "passive"))
    )
    (net (code "233") (name "unconnected-(X1-PadG2)") (class "Default")
      (node (ref "X1") (pin "G2") (pinfunction "G2_G2") (pintype "passive"))
    )
    (net (code "234") (name "unconnected-(X2-Pad1)") (class "Default")
      (node (ref "X2") (pin "1") (pinfunction "1_1") (pintype "passive"))
    )
    (net (code "235") (name "unconnected-(X2-Pad4)") (class "Default")
      (node (ref "X2") (pin "4") (pinfunction "4_4") (pintype "passive"))
    )
    (net (code "236") (name "unconnected-(X2-Pad5)") (class "Default")
      (node (ref "X2") (pin "5") (pinfunction "5_5") (pintype "passive"))
    )
    (net (code "237") (name "unconnected-(X2-Pad8)") (class "Default")
      (node (ref "X2") (pin "8") (pinfunction "8_8") (pintype "passive"))
    )
    (net (code "238") (name "unconnected-(X2-Pad9)") (class "Default")
      (node (ref "X2") (pin "9") (pinfunction "9_9") (pintype "passive"))
    )
    (net (code "239") (name "unconnected-(X2-PadG1)") (class "Default")
      (node (ref "X2") (pin "G1") (pinfunction "G1_G1") (pintype "passive"))
    )
    (net (code "240") (name "unconnected-(X2-PadG2)") (class "Default")
      (node (ref "X2") (pin "G2") (pinfunction "G2_G2") (pintype "passive"))
    )
    (net (code "241") (name "unconnected-(X3-NC-PadP7)") (class "Default")
      (node (ref "X3") (pin "P7") (pinfunction "NC_P7") (pintype "passive"))
    )
  )
)
